# dji_3s_battery.net
KiCad netlist of a schematic drawn in Altium Designer
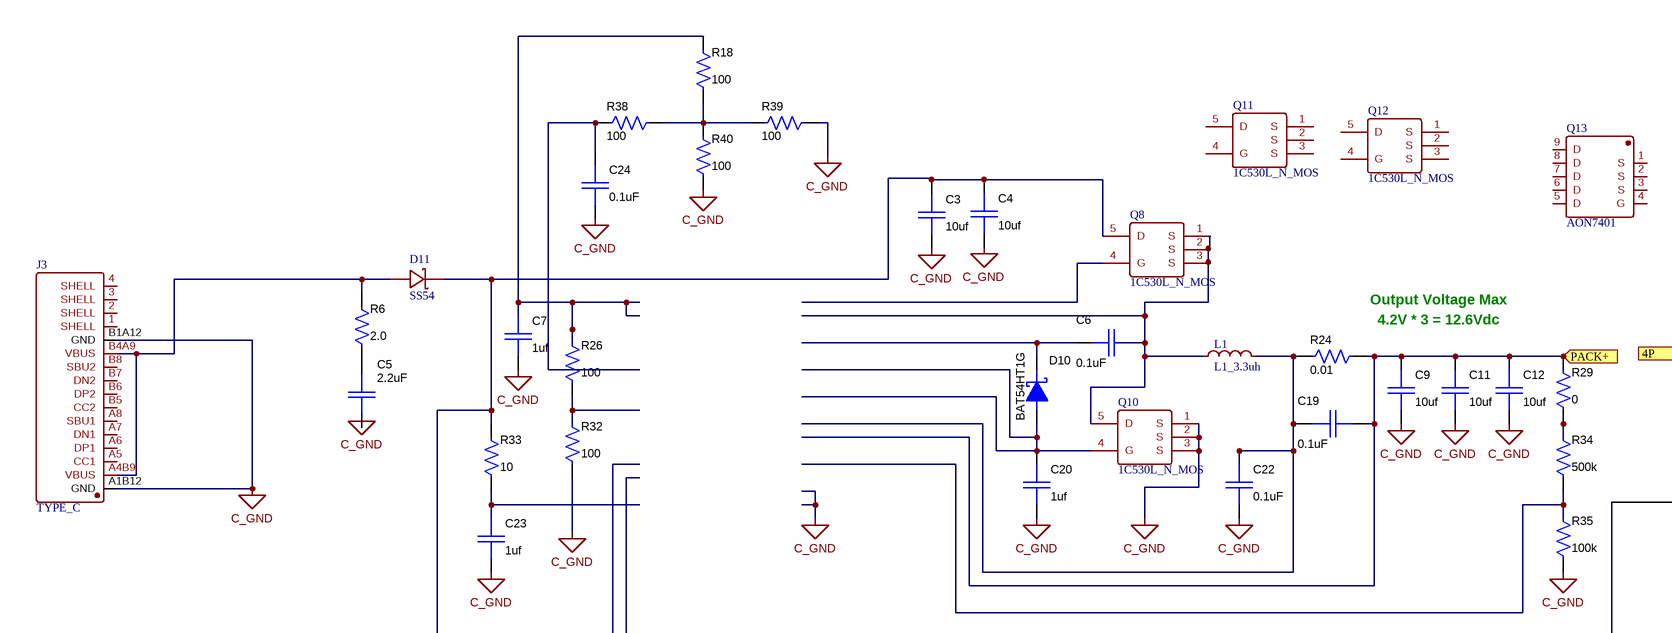
[diagram p0: dji_3s_battery.SchDoc, top left]
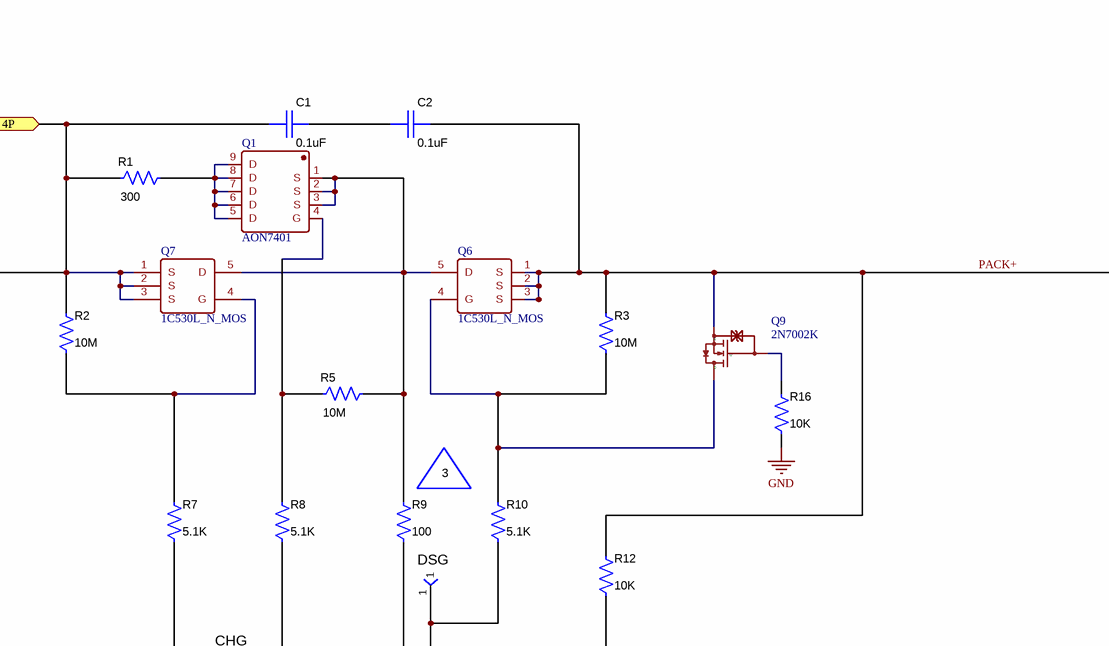
[diagram p1: dji_3s_battery.SchDoc, top right]
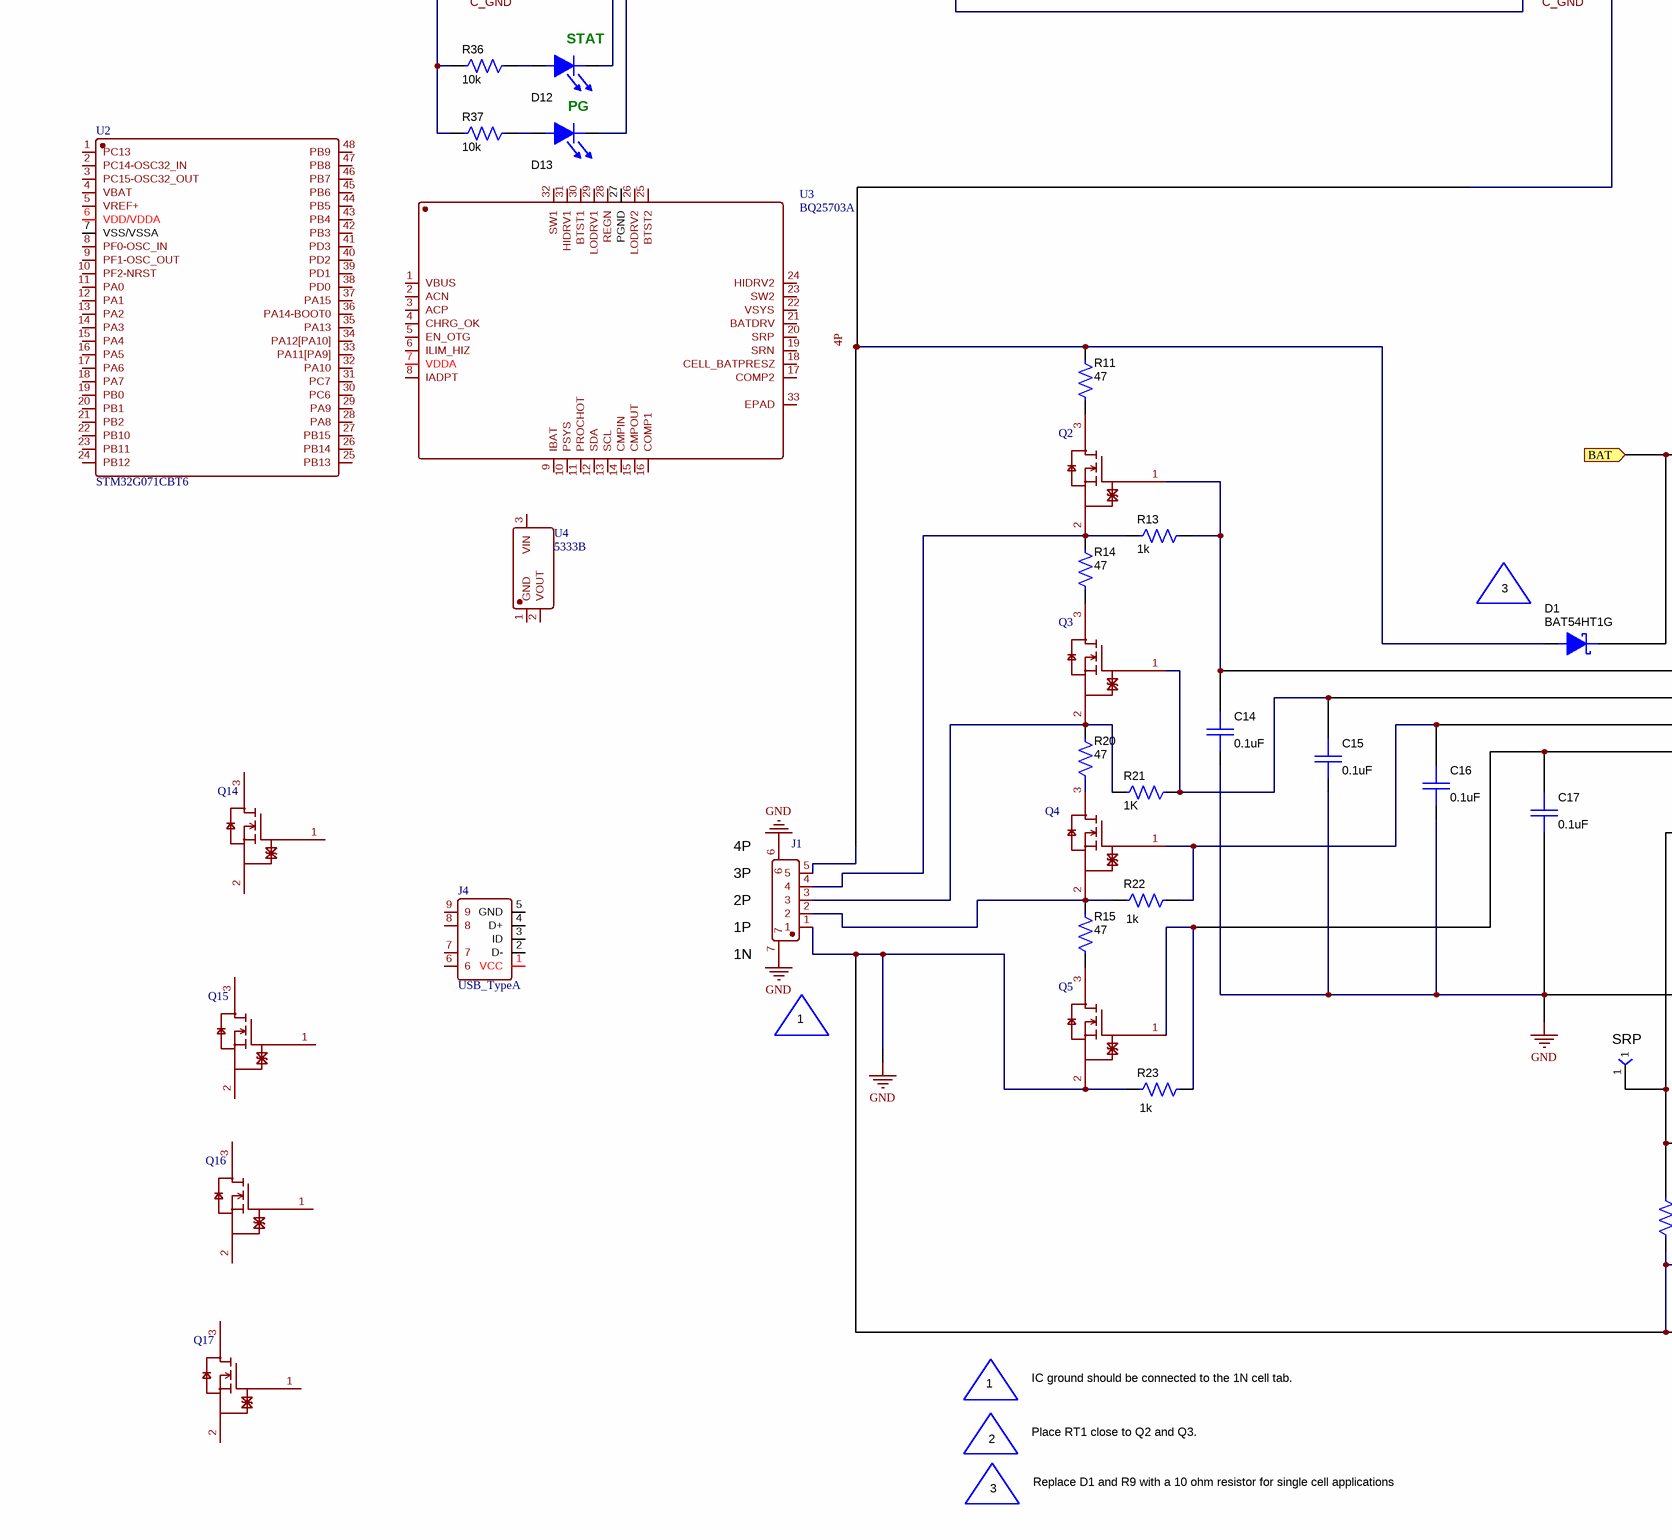
[diagram p2: dji_3s_battery.SchDoc, bottom left]
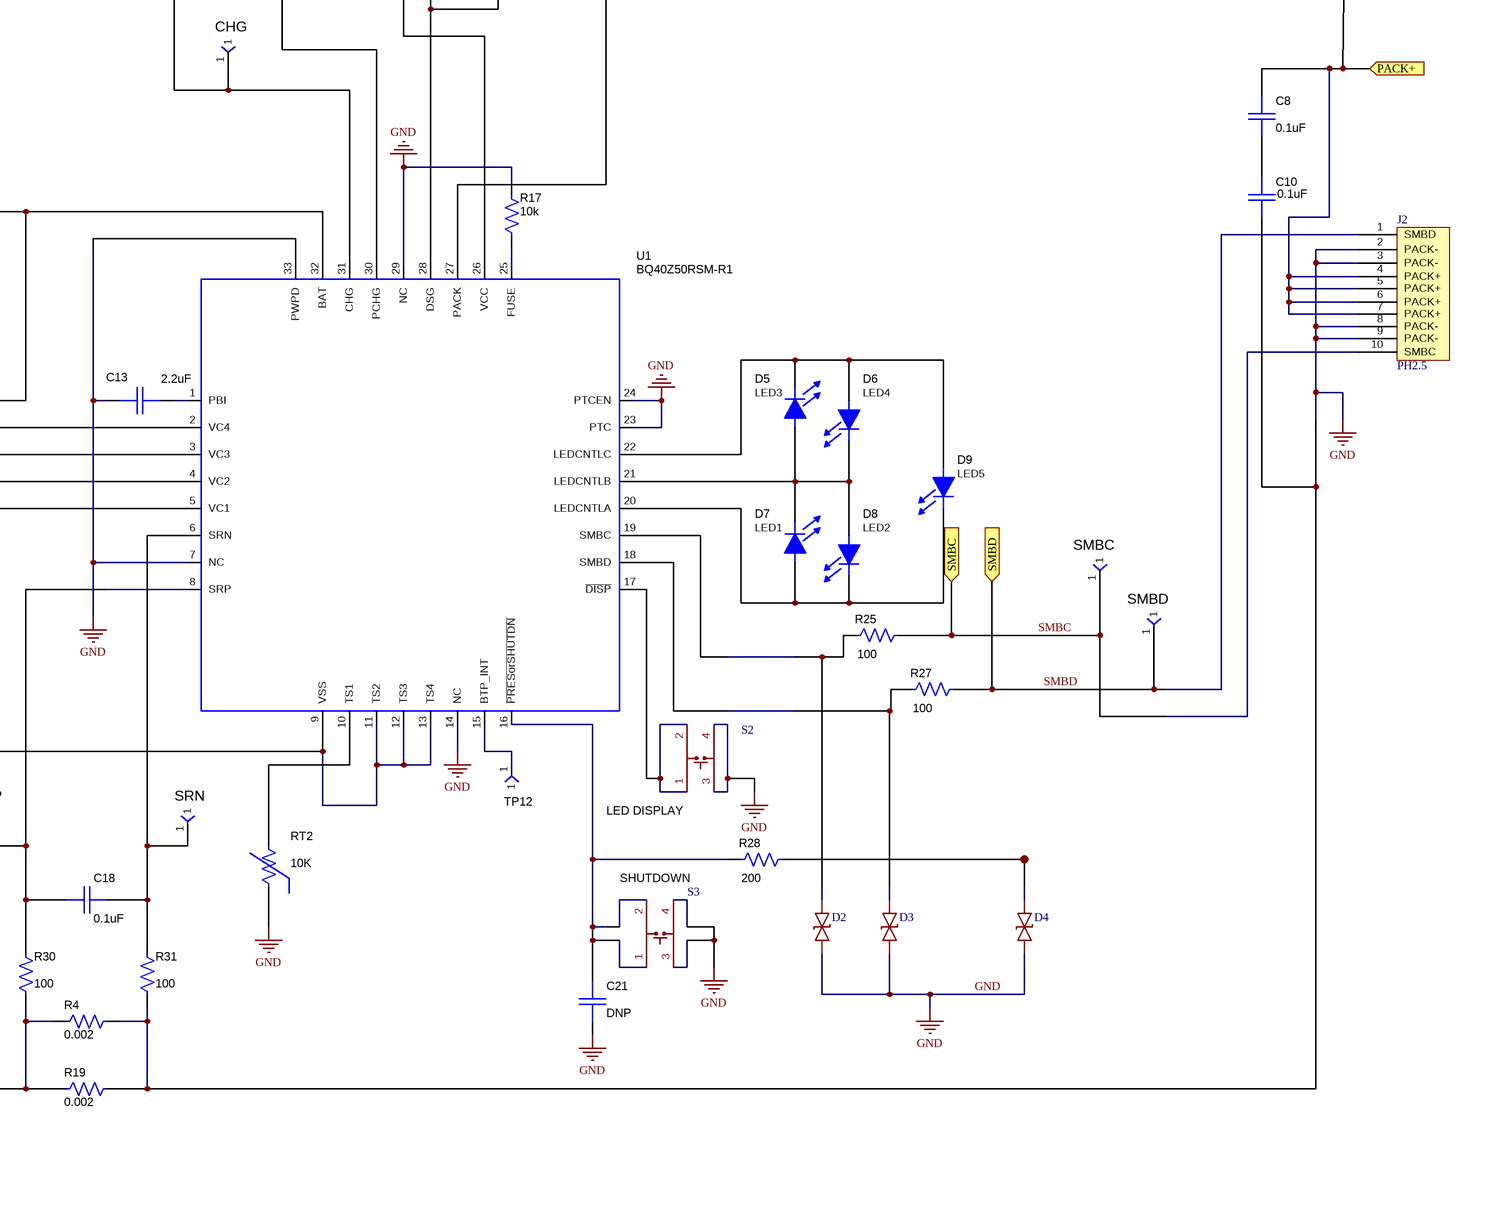
[diagram p3: dji_3s_battery.SchDoc, bottom right]

(export (version "E")
  (design (tool "Eeschema 10.0.6"))
  (components
    (comp (ref "C1")
      (value "0.1uF")
      (footprint "C603")
      (description "Capacitor, Ceramic Chip, 50V, X7R, ±20%")
      (fields (field (name "MANUFACTURER") "Kemet") (field (name "PARTNUMBER") "C0603C104M5RACTU"))
      (libsource (lib "PADSlegacy_Passive") (part "C0603"))
    )
    (comp (ref "C2")
      (value "0.1uF")
      (footprint "C603")
      (description "Capacitor, Ceramic Chip, 50V, X7R, ±20%")
      (fields (field (name "MANUFACTURER") "Kemet") (field (name "PARTNUMBER") "C0603C104M5RACTU"))
      (libsource (lib "PADSlegacy_Passive") (part "C0603"))
    )
    (comp (ref "C3")
      (value "10uf")
      (footprint "C603")
      (description "Capacitor, Ceramic Chip, 50V, X7R, ±20%")
      (fields (field (name "MANUFACTURER") "Kemet") (field (name "PARTNUMBER") "C0603C104M5RACTU"))
      (libsource (lib "PADSlegacy_Passive") (part "C0603"))
    )
    (comp (ref "C4")
      (value "10uf")
      (footprint "C603")
      (description "Capacitor, Ceramic Chip, 50V, X7R, ±20%")
      (fields (field (name "MANUFACTURER") "Kemet") (field (name "PARTNUMBER") "C0603C104M5RACTU"))
      (libsource (lib "PADSlegacy_Passive") (part "C0603"))
    )
    (comp (ref "C5")
      (value "2.2uF")
      (footprint "C0805")
      (description "Capacitor, Ceramic Chip, 25V, X7R ±20%")
      (fields (field (name "MANUFACTURER") "TDK") (field (name "PARTNUMBER") "C2012X7R1E225M085AB"))
      (libsource (lib "PADSlegacy_Passive") (part "C0805"))
    )
    (comp (ref "C6")
      (value "0.1uF")
      (footprint "C603")
      (description "Capacitor, Ceramic Chip, 50V, X7R, ±20%")
      (fields (field (name "MANUFACTURER") "Kemet") (field (name "PARTNUMBER") "C0603C104M5RACTU"))
      (libsource (lib "PADSlegacy_Passive") (part "C0603"))
    )
    (comp (ref "C7")
      (value "1uf")
      (footprint "C603")
      (description "Capacitor, Ceramic Chip, 50V, X7R, ±20%")
      (fields (field (name "MANUFACTURER") "Kemet") (field (name "PARTNUMBER") "C0603C104M5RACTU"))
      (libsource (lib "PADSlegacy_Passive") (part "C0603"))
    )
    (comp (ref "C8")
      (value "0.1uF")
      (footprint "C603")
      (description "Capacitor, Ceramic Chip, 50V, X7R, ±20%")
      (fields (field (name "MANUFACTURER") "Kemet") (field (name "PARTNUMBER") "C0603C104M5RACTU"))
      (libsource (lib "PADSlegacy_Passive") (part "C0603"))
    )
    (comp (ref "C9")
      (value "10uf")
      (footprint "C603")
      (description "Capacitor, Ceramic Chip, 50V, X7R, ±20%")
      (fields (field (name "MANUFACTURER") "Kemet") (field (name "PARTNUMBER") "C0603C104M5RACTU"))
      (libsource (lib "PADSlegacy_Passive") (part "C0603"))
    )
    (comp (ref "C10")
      (value "0.1uF")
      (footprint "C603")
      (description "Capacitor, Ceramic Chip, 50V, X7R, ±20%")
      (fields (field (name "MANUFACTURER") "Kemet") (field (name "PARTNUMBER") "C0603C104M5RACTU"))
      (libsource (lib "PADSlegacy_Passive") (part "C0603"))
    )
    (comp (ref "C11")
      (value "10uf")
      (footprint "C603")
      (description "Capacitor, Ceramic Chip, 50V, X7R, ±20%")
      (fields (field (name "MANUFACTURER") "Kemet") (field (name "PARTNUMBER") "C0603C104M5RACTU"))
      (libsource (lib "PADSlegacy_Passive") (part "C0603"))
    )
    (comp (ref "C12")
      (value "10uf")
      (footprint "C603")
      (description "Capacitor, Ceramic Chip, 50V, X7R, ±20%")
      (fields (field (name "MANUFACTURER") "Kemet") (field (name "PARTNUMBER") "C0603C104M5RACTU"))
      (libsource (lib "PADSlegacy_Passive") (part "C0603"))
    )
    (comp (ref "C13")
      (value "2.2uF")
      (footprint "C0805")
      (description "Capacitor, Ceramic Chip, 25V, X7R ±20%")
      (fields (field (name "MANUFACTURER") "TDK") (field (name "PARTNUMBER") "C2012X7R1E225M085AB"))
      (libsource (lib "PADSlegacy_Passive") (part "C0805"))
    )
    (comp (ref "C14")
      (value "0.1uF")
      (footprint "C603")
      (description "Capacitor, Ceramic Chip, 50V, X7R, ±20%")
      (fields (field (name "MANUFACTURER") "Kemet") (field (name "PARTNUMBER") "C0603C104M5RACTU"))
      (libsource (lib "PADSlegacy_Passive") (part "C0603"))
    )
    (comp (ref "C15")
      (value "0.1uF")
      (footprint "C603")
      (description "Capacitor, Ceramic Chip, 50V, X7R, ±20%")
      (fields (field (name "MANUFACTURER") "Kemet") (field (name "PARTNUMBER") "C0603C104M5RACTU"))
      (libsource (lib "PADSlegacy_Passive") (part "C0603"))
    )
    (comp (ref "C16")
      (value "0.1uF")
      (footprint "C603")
      (description "Capacitor, Ceramic Chip, 50V, X7R, ±20%")
      (fields (field (name "MANUFACTURER") "Kemet") (field (name "PARTNUMBER") "C0603C104M5RACTU"))
      (libsource (lib "PADSlegacy_Passive") (part "C0603"))
    )
    (comp (ref "C17")
      (value "0.1uF")
      (footprint "C603")
      (description "Capacitor, Ceramic Chip, 50V, X7R, ±20%")
      (fields (field (name "MANUFACTURER") "Kemet") (field (name "PARTNUMBER") "C0603C104M5RACTU"))
      (libsource (lib "PADSlegacy_Passive") (part "C0603"))
    )
    (comp (ref "C18")
      (value "0.1uF")
      (footprint "C603")
      (description "Capacitor, Ceramic Chip, 50V, X7R, ±20%")
      (fields (field (name "MANUFACTURER") "Kemet") (field (name "PARTNUMBER") "C0603C104M5RACTU"))
      (libsource (lib "PADSlegacy_Passive") (part "C0603"))
    )
    (comp (ref "C19")
      (value "0.1uF")
      (footprint "C603")
      (description "Capacitor, Ceramic Chip, 50V, X7R, ±20%")
      (fields (field (name "MANUFACTURER") "Kemet") (field (name "PARTNUMBER") "C0603C104M5RACTU"))
      (libsource (lib "PADSlegacy_Passive") (part "C0603"))
    )
    (comp (ref "C20")
      (value "1uf")
      (footprint "C603")
      (description "Capacitor, Ceramic Chip, 50V, X7R, ±20%")
      (fields (field (name "MANUFACTURER") "Kemet") (field (name "PARTNUMBER") "C0603C104M5RACTU"))
      (libsource (lib "PADSlegacy_Passive") (part "C0603"))
    )
    (comp (ref "C21")
      (value "DNP")
      (footprint "C603")
      (description "Capacitor, Ceramic Chip, 50V, X7R, ±20%")
      (fields (field (name "MANUFACTURER") "Kemet") (field (name "PARTNUMBER") "C0603C104M5RACTU"))
      (libsource (lib "PADSlegacy_Passive") (part "C0603"))
    )
    (comp (ref "C22")
      (value "0.1uF")
      (footprint "C603")
      (description "Capacitor, Ceramic Chip, 50V, X7R, ±20%")
      (fields (field (name "MANUFACTURER") "Kemet") (field (name "PARTNUMBER") "C0603C104M5RACTU"))
      (libsource (lib "PADSlegacy_Passive") (part "C0603"))
    )
    (comp (ref "C23")
      (value "1uf")
      (footprint "C603")
      (description "Capacitor, Ceramic Chip, 50V, X7R, ±20%")
      (fields (field (name "MANUFACTURER") "Kemet") (field (name "PARTNUMBER") "C0603C104M5RACTU"))
      (libsource (lib "PADSlegacy_Passive") (part "C0603"))
    )
    (comp (ref "C24")
      (value "0.1uF")
      (footprint "C603")
      (description "Capacitor, Ceramic Chip, 50V, X7R, ±20%")
      (fields (field (name "MANUFACTURER") "Kemet") (field (name "PARTNUMBER") "C0603C104M5RACTU"))
      (libsource (lib "PADSlegacy_Passive") (part "C0603"))
    )
    (comp (ref "D1")
      (value "BAT54HT1G")
      (footprint "SOD-323")
      (description "Diode, Schottky, 200-mA, 30-V")
      (fields (field (name "MANUFACTURER") "On Semi") (field (name "Comment") "D-BAT54HT1"))
      (libsource (lib "PADSlegacy_Active") (part "D-BAT54HT1"))
    )
    (comp (ref "D2")
      (value "ESD_Diode")
      (footprint "ESD_Diode")
      (libsource (lib "BQ4050") (part "ESD_Diode"))
    )
    (comp (ref "D3")
      (value "ESD_Diode")
      (footprint "ESD_Diode")
      (libsource (lib "BQ4050") (part "ESD_Diode"))
    )
    (comp (ref "D4")
      (value "ESD_Diode")
      (footprint "ESD_Diode")
      (libsource (lib "BQ4050") (part "ESD_Diode"))
    )
    (comp (ref "D5")
      (value "D_LED_SML-LXR1206USBC-TR")
      (footprint "LED0805")
      (description "Diode, LED, 2X3mm 565nm GRN WTR CLR SMD")
      (fields (field (name "PARTNUMBER") "SML-LX23GC") (field (name "MANUFACTURER") "Lumex"))
      (libsource (lib "PADSlegacy_Active") (part "D_LED_SML-LXR1206USBC-TR"))
    )
    (comp (ref "D6")
      (value "D_LED_SML-LXR1206USBC-TR")
      (footprint "LED0805")
      (description "Diode, LED, 2X3mm 565nm GRN WTR CLR SMD")
      (fields (field (name "PARTNUMBER") "SML-LX23GC") (field (name "MANUFACTURER") "Lumex"))
      (libsource (lib "PADSlegacy_Active") (part "D_LED_SML-LXR1206USBC-TR"))
    )
    (comp (ref "D7")
      (value "D_LED_SML-LXR1206USBC-TR")
      (footprint "LED0805")
      (description "Diode, LED, 2X3mm 565nm GRN WTR CLR SMD")
      (fields (field (name "PARTNUMBER") "SML-LX23GC") (field (name "MANUFACTURER") "Lumex"))
      (libsource (lib "PADSlegacy_Active") (part "D_LED_SML-LXR1206USBC-TR"))
    )
    (comp (ref "D8")
      (value "D_LED_SML-LXR1206USBC-TR")
      (footprint "LED0805")
      (description "Diode, LED, 2X3mm 565nm GRN WTR CLR SMD")
      (fields (field (name "PARTNUMBER") "SML-LX23GC") (field (name "MANUFACTURER") "Lumex"))
      (libsource (lib "PADSlegacy_Active") (part "D_LED_SML-LXR1206USBC-TR"))
    )
    (comp (ref "D9")
      (value "D_LED_SML-LXR1206USBC-TR")
      (footprint "LED0805")
      (description "Diode, LED, 2X3mm 565nm GRN WTR CLR SMD")
      (fields (field (name "PARTNUMBER") "SML-LX23GC") (field (name "MANUFACTURER") "Lumex"))
      (libsource (lib "PADSlegacy_Active") (part "D_LED_SML-LXR1206USBC-TR"))
    )
    (comp (ref "D10")
      (value "BAT54HT1G")
      (footprint "SOD-323")
      (description "Diode, Schottky, 200-mA, 30-V")
      (fields (field (name "MANUFACTURER") "On Semi") (field (name "Comment") "D-BAT54HT1"))
      (libsource (lib "PADSlegacy_Active") (part "D-BAT54HT1"))
    )
    (comp (ref "D11") (value "SS54") (footprint "SMA(DO-214AC)") (libsource (lib "BQ4050") (part "SS54")))
    (comp (ref "D12")
      (value "D_LED_SML-LXR1206USBC-TR")
      (footprint "LED0805")
      (description "Diode, LED, 2X3mm 565nm GRN WTR CLR SMD")
      (fields (field (name "PARTNUMBER") "SML-LX23GC") (field (name "MANUFACTURER") "Lumex"))
      (libsource (lib "PADSlegacy_Active") (part "D_LED_SML-LXR1206USBC-TR"))
    )
    (comp (ref "D13")
      (value "D_LED_SML-LXR1206USBC-TR")
      (footprint "LED0805")
      (description "Diode, LED, 2X3mm 565nm GRN WTR CLR SMD")
      (fields (field (name "PARTNUMBER") "SML-LX23GC") (field (name "MANUFACTURER") "Lumex"))
      (libsource (lib "PADSlegacy_Active") (part "D_LED_SML-LXR1206USBC-TR"))
    )
    (comp (ref "J1") (value "SMD_1.25") (footprint "SMD_1.25") (libsource (lib "BQ4050") (part "SMD_1.25")))
    (comp (ref "J2") (value "PH2.5") (footprint "PH2.5") (libsource (lib "BQ4050") (part "PH2.5")))
    (comp (ref "J3") (value "TYPE_C") (footprint "TYPE_C") (libsource (lib "BQ4050") (part "TYPE_C")))
    (comp (ref "J4")
      (value "USB_TypeA")
      (footprint "USB_TypeA")
      (libsource (lib "BQ4050") (part "USB_TypeA"))
    )
    (comp (ref "L1") (value "L1_3.3uh") (footprint "3.3uh") (libsource (lib "BQ4050") (part "L1_3.3uh")))
    (comp (ref "Q1") (value "AON7401") (footprint "DFN-8") (libsource (lib "BQ4050") (part "AON7401")))
    (comp (ref "Q2")
      (value "DMN601K")
      (footprint "SOT-23 - duplicate")
      (libsource (lib "BQ4050") (part "DMN601K"))
    )
    (comp (ref "Q3")
      (value "DMN601K")
      (footprint "SOT-23 - duplicate")
      (libsource (lib "BQ4050") (part "DMN601K"))
    )
    (comp (ref "Q4")
      (value "DMN601K")
      (footprint "SOT-23 - duplicate")
      (libsource (lib "BQ4050") (part "DMN601K"))
    )
    (comp (ref "Q5")
      (value "DMN601K")
      (footprint "SOT-23 - duplicate")
      (libsource (lib "BQ4050") (part "DMN601K"))
    )
    (comp (ref "Q6")
      (value "1C530L_N_MOS")
      (footprint "LFPAK")
      (libsource (lib "BQ4050") (part "1C530L_N_MOS"))
    )
    (comp (ref "Q7")
      (value "1C530L_N_MOS")
      (footprint "LFPAK")
      (libsource (lib "BQ4050") (part "1C530L_N_MOS"))
    )
    (comp (ref "Q8")
      (value "1C530L_N_MOS")
      (footprint "LFPAK")
      (libsource (lib "BQ4050") (part "1C530L_N_MOS"))
    )
    (comp (ref "Q9") (value "2N7002K") (footprint "2N7002K") (libsource (lib "BQ4050") (part "2N7002K")))
    (comp (ref "Q10")
      (value "1C530L_N_MOS")
      (footprint "LFPAK")
      (libsource (lib "BQ4050") (part "1C530L_N_MOS"))
    )
    (comp (ref "Q11")
      (value "1C530L_N_MOS")
      (footprint "LFPAK")
      (libsource (lib "BQ4050") (part "1C530L_N_MOS"))
    )
    (comp (ref "Q12")
      (value "1C530L_N_MOS")
      (footprint "LFPAK")
      (libsource (lib "BQ4050") (part "1C530L_N_MOS"))
    )
    (comp (ref "Q13") (value "AON7401") (footprint "DFN-8") (libsource (lib "BQ4050") (part "AON7401")))
    (comp (ref "Q14")
      (value "DMN601K")
      (footprint "SOT-23 - duplicate")
      (libsource (lib "BQ4050") (part "DMN601K"))
    )
    (comp (ref "Q15")
      (value "DMN601K")
      (footprint "SOT-23 - duplicate")
      (libsource (lib "BQ4050") (part "DMN601K"))
    )
    (comp (ref "Q16")
      (value "DMN601K")
      (footprint "SOT-23 - duplicate")
      (libsource (lib "BQ4050") (part "DMN601K"))
    )
    (comp (ref "Q17")
      (value "DMN601K")
      (footprint "SOT-23 - duplicate")
      (libsource (lib "BQ4050") (part "DMN601K"))
    )
    (comp (ref "R1")
      (value "300")
      (footprint "R2512")
      (description "Resistor, Chip 1W, 5%")
      (fields (field (name "PARTNUMBER") "CRCW2512300RJNEG") (field (name "MANUFACTURER") "Vishay-Dale"))
      (libsource (lib "PADSlegacy_Passive") (part "R2512_5%"))
    )
    (comp (ref "R2")
      (value "10M")
      (footprint "0603")
      (description "Resistor, Chip, 1/10W, 5%")
      (fields (field (name "PARTNUMBER") "CRCW060310M0JNEA") (field (name "MANUFACTURER") "Vishay-Dale"))
      (libsource (lib "PADSlegacy_Passive") (part "R0603_1%"))
    )
    (comp (ref "R3")
      (value "10M")
      (footprint "0603")
      (description "Resistor, Chip, 1/10W, 5%")
      (fields (field (name "PARTNUMBER") "CRCW060310M0JNEA") (field (name "MANUFACTURER") "Vishay-Dale"))
      (libsource (lib "PADSlegacy_Passive") (part "R0603_1%"))
    )
    (comp (ref "R4")
      (value "0.002")
      (footprint "R2512")
      (description "Resistor, Chip 1W, 5%")
      (fields (field (name "PARTNUMBER") "CRCW2512300RJNEG") (field (name "MANUFACTURER") "Vishay-Dale"))
      (libsource (lib "BQ4050") (part "R2512_5%"))
    )
    (comp (ref "R5")
      (value "10M")
      (footprint "0603")
      (description "Resistor, Chip, 1/10W, 5%")
      (fields (field (name "PARTNUMBER") "CRCW060310M0JNEA") (field (name "MANUFACTURER") "Vishay-Dale"))
      (libsource (lib "PADSlegacy_Passive") (part "R0603_1%"))
    )
    (comp (ref "R6")
      (value "2.0")
      (footprint "0603")
      (description "Resistor, Chip, 1/10W, 5%")
      (fields (field (name "PARTNUMBER") "CRCW0603100RJNEAHP") (field (name "MANUFACTURER") "Vishay-Dale"))
      (libsource (lib "PADSlegacy_Passive") (part "R0603_1%"))
    )
    (comp (ref "R7")
      (value "5.1K")
      (footprint "0603")
      (description "Resistor, Chip, 1/10W, 5%")
      (fields (field (name "PARTNUMBER") "CRCW06035K10JNEA") (field (name "MANUFACTURER") "Vishay-Dale"))
      (libsource (lib "PADSlegacy_Passive") (part "R0603_1%"))
    )
    (comp (ref "R8")
      (value "5.1K")
      (footprint "0603")
      (description "Resistor, Chip, 1/10W, 5%")
      (fields (field (name "PARTNUMBER") "CRCW06035K10JNEA") (field (name "MANUFACTURER") "Vishay-Dale"))
      (libsource (lib "PADSlegacy_Passive") (part "R0603_1%"))
    )
    (comp (ref "R9")
      (value "100")
      (footprint "0603")
      (description "Resistor, Chip, 1/10W, 5%")
      (fields (field (name "PARTNUMBER") "CRCW0603100RJNEAHP") (field (name "MANUFACTURER") "Vishay-Dale"))
      (libsource (lib "PADSlegacy_Passive") (part "R0603_1%"))
    )
    (comp (ref "R10")
      (value "5.1K")
      (footprint "0603")
      (description "Resistor, Chip, 1/10W, 5%")
      (fields (field (name "PARTNUMBER") "CRCW06035K10JNEA") (field (name "MANUFACTURER") "Vishay-Dale"))
      (libsource (lib "PADSlegacy_Passive") (part "R0603_1%"))
    )
    (comp (ref "R11")
      (value "47")
      (footprint "R1206")
      (description "Resistor, Chip 1 watt, ±1%, 50 ppm")
      (fields (field (name "PARTNUMBER") "CSR1206-0R001F1") (field (name "MANUFACTURER") "Reidon"))
      (libsource (lib "BQ4050") (part "R1206_1%"))
    )
    (comp (ref "R12")
      (value "10K")
      (footprint "0603")
      (description "Resistor, Chip, 1/10W, 5%")
      (fields (field (name "PARTNUMBER") "CRCW060310K0JNEA") (field (name "MANUFACTURER") "Vishay-Dale"))
      (libsource (lib "PADSlegacy_Passive") (part "R0603_1%"))
    )
    (comp (ref "R13")
      (value "1k")
      (footprint "0603")
      (description "Resistor, Chip, 1/10W, 5%")
      (fields (field (name "PARTNUMBER") "CRCW0603100RJNEAHP") (field (name "MANUFACTURER") "Vishay-Dale"))
      (libsource (lib "PADSlegacy_Passive") (part "R0603_1%"))
    )
    (comp (ref "R14")
      (value "47")
      (footprint "R1206")
      (description "Resistor, Chip 1 watt, ±1%, 50 ppm")
      (fields (field (name "PARTNUMBER") "CSR1206-0R001F1") (field (name "MANUFACTURER") "Reidon"))
      (libsource (lib "BQ4050") (part "R1206_1%"))
    )
    (comp (ref "R15")
      (value "47")
      (footprint "R1206")
      (description "Resistor, Chip 1 watt, ±1%, 50 ppm")
      (fields (field (name "PARTNUMBER") "CSR1206-0R001F1") (field (name "MANUFACTURER") "Reidon"))
      (libsource (lib "BQ4050") (part "R1206_1%"))
    )
    (comp (ref "R16")
      (value "10K")
      (footprint "0603")
      (description "Resistor, Chip, 1/10W, 5%")
      (fields (field (name "PARTNUMBER") "CRCW060310M0JNEA") (field (name "MANUFACTURER") "Vishay-Dale"))
      (libsource (lib "PADSlegacy_Passive") (part "R0603_1%"))
    )
    (comp (ref "R17")
      (value "10k")
      (footprint "0603")
      (description "Resistor, Chip, 1/10W, 5%")
      (fields (field (name "PARTNUMBER") "CRCW06035K10JNEA") (field (name "MANUFACTURER") "Vishay-Dale"))
      (libsource (lib "PADSlegacy_Passive") (part "R0603_1%"))
    )
    (comp (ref "R18")
      (value "100")
      (footprint "0603")
      (description "Resistor, Chip, 1/10W, 5%")
      (fields (field (name "PARTNUMBER") "CRCW0603100RJNEAHP") (field (name "MANUFACTURER") "Vishay-Dale"))
      (libsource (lib "PADSlegacy_Passive") (part "R0603_1%"))
    )
    (comp (ref "R19")
      (value "0.002")
      (footprint "R2512")
      (description "Resistor, Chip 1W, 5%")
      (fields (field (name "PARTNUMBER") "CRCW2512300RJNEG") (field (name "MANUFACTURER") "Vishay-Dale"))
      (libsource (lib "BQ4050") (part "R2512_5%"))
    )
    (comp (ref "R20")
      (value "47")
      (footprint "R1206")
      (description "Resistor, Chip 1 watt, ±1%, 50 ppm")
      (fields (field (name "PARTNUMBER") "CSR1206-0R001F1") (field (name "MANUFACTURER") "Reidon"))
      (libsource (lib "BQ4050") (part "R1206_1%"))
    )
    (comp (ref "R21")
      (value "1K")
      (footprint "0603")
      (description "Resistor, Chip, 1/10W, 5%")
      (fields (field (name "PARTNUMBER") "CRCW0603100RJNEAHP") (field (name "MANUFACTURER") "Vishay-Dale"))
      (libsource (lib "PADSlegacy_Passive") (part "R0603_1%"))
    )
    (comp (ref "R22")
      (value "1k")
      (footprint "0603")
      (description "Resistor, Chip, 1/10W, 5%")
      (fields (field (name "PARTNUMBER") "CRCW0603100RJNEAHP") (field (name "MANUFACTURER") "Vishay-Dale"))
      (libsource (lib "PADSlegacy_Passive") (part "R0603_1%"))
    )
    (comp (ref "R23")
      (value "1k")
      (footprint "0603")
      (description "Resistor, Chip, 1/10W, 5%")
      (fields (field (name "PARTNUMBER") "CRCW0603100RJNEAHP") (field (name "MANUFACTURER") "Vishay-Dale"))
      (libsource (lib "PADSlegacy_Passive") (part "R0603_1%"))
    )
    (comp (ref "R24")
      (value "0.01")
      (footprint "R2512")
      (description "Resistor, Chip 1W, 5%")
      (fields (field (name "PARTNUMBER") "CRCW2512300RJNEG") (field (name "MANUFACTURER") "Vishay-Dale"))
      (libsource (lib "BQ4050") (part "R2512_5%"))
    )
    (comp (ref "R25")
      (value "100")
      (footprint "0603")
      (description "Resistor, Chip, 1/10W, 5%")
      (fields (field (name "PARTNUMBER") "CRCW0603100RJNEAHP") (field (name "MANUFACTURER") "Vishay-Dale"))
      (libsource (lib "PADSlegacy_Passive") (part "R0603_1%"))
    )
    (comp (ref "R26")
      (value "100")
      (footprint "0603")
      (description "Resistor, Chip, 1/10W, 5%")
      (fields (field (name "PARTNUMBER") "CRCW0603100RJNEAHP") (field (name "MANUFACTURER") "Vishay-Dale"))
      (libsource (lib "PADSlegacy_Passive") (part "R0603_1%"))
    )
    (comp (ref "R27")
      (value "100")
      (footprint "0603")
      (description "Resistor, Chip, 1/10W, 5%")
      (fields (field (name "PARTNUMBER") "CRCW0603100RJNEAHP") (field (name "MANUFACTURER") "Vishay-Dale"))
      (libsource (lib "PADSlegacy_Passive") (part "R0603_1%"))
    )
    (comp (ref "R28")
      (value "200")
      (footprint "0603")
      (description "Resistor, Chip, 1/16W, 5%")
      (fields (field (name "PARTNUMBER") "CRCW0603200RJNEA") (field (name "MANUFACTURER") "Vishay-Dale"))
      (libsource (lib "PADSlegacy_Passive") (part "R0603_1%"))
    )
    (comp (ref "R29")
      (value "0")
      (footprint "0603")
      (description "Resistor, Chip, 1/10W, 5%")
      (fields (field (name "PARTNUMBER") "CRCW0603100RJNEAHP") (field (name "MANUFACTURER") "Vishay-Dale"))
      (libsource (lib "PADSlegacy_Passive") (part "R0603_1%"))
    )
    (comp (ref "R30")
      (value "100")
      (footprint "0603")
      (description "Resistor, Chip, 1/10W, 5%")
      (fields (field (name "PARTNUMBER") "CRCW0603100RJNEAHP") (field (name "MANUFACTURER") "Vishay-Dale"))
      (libsource (lib "PADSlegacy_Passive") (part "R0603_1%"))
    )
    (comp (ref "R31")
      (value "100")
      (footprint "0603")
      (description "Resistor, Chip, 1/10W, 5%")
      (fields (field (name "PARTNUMBER") "CRCW0603100RJNEAHP") (field (name "MANUFACTURER") "Vishay-Dale"))
      (libsource (lib "PADSlegacy_Passive") (part "R0603_1%"))
    )
    (comp (ref "R32")
      (value "100")
      (footprint "0603")
      (description "Resistor, Chip, 1/10W, 5%")
      (fields (field (name "PARTNUMBER") "CRCW0603100RJNEAHP") (field (name "MANUFACTURER") "Vishay-Dale"))
      (libsource (lib "PADSlegacy_Passive") (part "R0603_1%"))
    )
    (comp (ref "R33")
      (value "10")
      (footprint "0603")
      (description "Resistor, Chip, 1/10W, 5%")
      (fields (field (name "PARTNUMBER") "CRCW0603100RJNEAHP") (field (name "MANUFACTURER") "Vishay-Dale"))
      (libsource (lib "PADSlegacy_Passive") (part "R0603_1%"))
    )
    (comp (ref "R34")
      (value "500k")
      (footprint "0603")
      (description "Resistor, Chip, 1/10W, 5%")
      (fields (field (name "PARTNUMBER") "CRCW0603100RJNEAHP") (field (name "MANUFACTURER") "Vishay-Dale"))
      (libsource (lib "PADSlegacy_Passive") (part "R0603_1%"))
    )
    (comp (ref "R35")
      (value "100k")
      (footprint "0603")
      (description "Resistor, Chip, 1/10W, 5%")
      (fields (field (name "PARTNUMBER") "CRCW0603100RJNEAHP") (field (name "MANUFACTURER") "Vishay-Dale"))
      (libsource (lib "PADSlegacy_Passive") (part "R0603_1%"))
    )
    (comp (ref "R36")
      (value "10k")
      (footprint "0603")
      (description "Resistor, Chip, 1/10W, 5%")
      (fields (field (name "PARTNUMBER") "CRCW0603100RJNEAHP") (field (name "MANUFACTURER") "Vishay-Dale"))
      (libsource (lib "PADSlegacy_Passive") (part "R0603_1%"))
    )
    (comp (ref "R37")
      (value "10k")
      (footprint "0603")
      (description "Resistor, Chip, 1/10W, 5%")
      (fields (field (name "PARTNUMBER") "CRCW0603100RJNEAHP") (field (name "MANUFACTURER") "Vishay-Dale"))
      (libsource (lib "PADSlegacy_Passive") (part "R0603_1%"))
    )
    (comp (ref "R38")
      (value "100")
      (footprint "0603")
      (description "Resistor, Chip, 1/10W, 5%")
      (fields (field (name "PARTNUMBER") "CRCW0603100RJNEAHP") (field (name "MANUFACTURER") "Vishay-Dale"))
      (libsource (lib "PADSlegacy_Passive") (part "R0603_1%"))
    )
    (comp (ref "R39")
      (value "100")
      (footprint "0603")
      (description "Resistor, Chip, 1/10W, 5%")
      (fields (field (name "PARTNUMBER") "CRCW0603100RJNEAHP") (field (name "MANUFACTURER") "Vishay-Dale"))
      (libsource (lib "PADSlegacy_Passive") (part "R0603_1%"))
    )
    (comp (ref "R40")
      (value "100")
      (footprint "0603")
      (description "Resistor, Chip, 1/10W, 5%")
      (fields (field (name "PARTNUMBER") "CRCW0603100RJNEAHP") (field (name "MANUFACTURER") "Vishay-Dale"))
      (libsource (lib "PADSlegacy_Passive") (part "R0603_1%"))
    )
    (comp (ref "RT2")
      (value "10K")
      (footprint "C0805")
      (description "Thermistor, NTC, 3-A")
      (fields (field (name "MANUFACTURER") "Semitec") (field (name "PARTNUMBER") "103AT-2"))
      (libsource (lib "PADSlegacy_Passive") (part "THERMISTOR-103AT"))
    )
    (comp (ref "S2") (value "SW_SMD") (footprint "SW_SMD") (libsource (lib "BQ4050") (part "SW_SMD")))
    (comp (ref "S3") (value "SW_SMD") (footprint "SW_SMD") (libsource (lib "BQ4050") (part "SW_SMD")))
    (comp (ref "TP1")
      (value "TP_40_SMT")
      (footprint "TP_40_SMT")
      (description "Test point, 40 mil SMT")
      (fields (field (name "MANUFACTURER") "None"))
      (libsource (lib "PADSlegacy_Hardware") (part "TP_40_SMT"))
    )
    (comp (ref "TP2")
      (value "TP_.040_SMT")
      (footprint "TP_.040_SMT")
      (description "Test point, 40 mil SMT")
      (fields (field (name "MANUFACTURER") "None"))
      (libsource (lib "PADSlegacy_Hardware") (part "TP_.040_SMT"))
    )
    (comp (ref "TP5")
      (value "TP_.040_SMT")
      (footprint "TP_.040_SMT")
      (description "Test point, 40 mil SMT")
      (fields (field (name "MANUFACTURER") "None"))
      (libsource (lib "PADSlegacy_Hardware") (part "TP_.040_SMT"))
    )
    (comp (ref "TP6")
      (value "TP_.040_SMT")
      (footprint "TP_.040_SMT")
      (description "Test point, 40 mil SMT")
      (fields (field (name "MANUFACTURER") "None"))
      (libsource (lib "PADSlegacy_Hardware") (part "TP_.040_SMT"))
    )
    (comp (ref "TP9")
      (value "TP_.040_SMT")
      (footprint "TP_.040_SMT")
      (description "Test point, 40 mil SMT")
      (fields (field (name "MANUFACTURER") "None"))
      (libsource (lib "PADSlegacy_Hardware") (part "TP_.040_SMT"))
    )
    (comp (ref "TP10")
      (value "TP_.040_SMT")
      (footprint "TP_.040_SMT")
      (description "Test point, 40 mil SMT")
      (fields (field (name "MANUFACTURER") "None"))
      (libsource (lib "PADSlegacy_Hardware") (part "TP_.040_SMT"))
    )
    (comp (ref "TP12")
      (value "TP_40_SMT")
      (footprint "TP_40_SMT")
      (description "Test point, 40 mil SMT")
      (fields (field (name "MANUFACTURER") "None"))
      (libsource (lib "PADSlegacy_Hardware") (part "TP_40_SMT"))
    )
    (comp (ref "U1")
      (value "BQ40Z50RSM-R1")
      (footprint "QFP-32P_(RSM)")
      (description "IC, 2 to 4-Series Li-Ion Battery Pack Manager")
      (fields (field (name "MANUFACTURER") "TI") (field (name "Comment") "BQ40Z55RSM"))
      (libsource (lib "BQ4050") (part "BQ40Z55RSM"))
    )
    (comp (ref "U2")
      (value "STM32G071CBT6")
      (footprint "STM32G071CBT6")
      (libsource (lib "BQ4050") (part "STM32G071CBT6"))
    )
    (comp (ref "U3") (value "BQ25703A") (footprint "BQ25703A") (libsource (lib "BQ4050") (part "BQ25703A")))
    (comp (ref "U4")
      (value "5333B")
      (footprint "SOT-23 - duplicate")
      (libsource (lib "BQ4050") (part "5333B"))
    )
  )
  (nets
    (net (code "1") (name "/4P") (class "Default")
      (node (ref "C1") (pin "2") (pinfunction "2_2") (pintype "passive"))
      (node (ref "D1") (pin "2") (pinfunction "A_2") (pintype "passive"))
      (node (ref "J1") (pin "5") (pinfunction "5_5") (pintype "passive"))
      (node (ref "Q7") (pin "1") (pinfunction "S_1") (pintype "passive"))
      (node (ref "Q7") (pin "2") (pinfunction "S_2") (pintype "passive"))
      (node (ref "Q7") (pin "3") (pinfunction "S_3") (pintype "passive"))
      (node (ref "R1") (pin "1") (pinfunction "1_1") (pintype "passive"))
      (node (ref "R11") (pin "1") (pinfunction "1_1") (pintype "passive"))
      (node (ref "R2") (pin "2") (pinfunction "2_2") (pintype "passive"))
    )
    (net (code "2") (name "/BAT") (class "Default")
      (node (ref "D1") (pin "1") (pinfunction "C_1") (pintype "passive"))
      (node (ref "U1") (pin "32") (pinfunction "BAT_32") (pintype "passive"))
    )
    (net (code "3") (name "/PACK+") (class "Default")
      (node (ref "C11") (pin "2") (pinfunction "2_2") (pintype "passive"))
      (node (ref "C12") (pin "2") (pinfunction "2_2") (pintype "passive"))
      (node (ref "C19") (pin "1") (pinfunction "1_1") (pintype "passive"))
      (node (ref "C2") (pin "1") (pinfunction "1_1") (pintype "passive"))
      (node (ref "C8") (pin "2") (pinfunction "2_2") (pintype "passive"))
      (node (ref "C9") (pin "2") (pinfunction "2_2") (pintype "passive"))
      (node (ref "J2") (pin "4") (pinfunction "PACK+_4") (pintype "passive"))
      (node (ref "J2") (pin "5") (pinfunction "PACK+_5") (pintype "passive"))
      (node (ref "J2") (pin "6") (pinfunction "PACK+_6") (pintype "passive"))
      (node (ref "J2") (pin "7") (pinfunction "PACK+_7") (pintype "passive"))
      (node (ref "Q6") (pin "1") (pinfunction "S_1") (pintype "passive"))
      (node (ref "Q6") (pin "2") (pinfunction "S_2") (pintype "passive"))
      (node (ref "Q6") (pin "3") (pinfunction "S_3") (pintype "passive"))
      (node (ref "Q9") (pin "2") (pinfunction "S_2") (pintype "passive"))
      (node (ref "R12") (pin "2") (pinfunction "2_2") (pintype "passive"))
      (node (ref "R24") (pin "2") (pinfunction "2_2") (pintype "passive"))
      (node (ref "R29") (pin "2") (pinfunction "2_2") (pintype "passive"))
      (node (ref "R3") (pin "2") (pinfunction "2_2") (pintype "passive"))
    )
    (net (code "4") (name "/SMBC") (class "Default")
      (node (ref "J2") (pin "10") (pinfunction "SMBC_10") (pintype "passive"))
      (node (ref "R25") (pin "2") (pinfunction "2_2") (pintype "passive"))
      (node (ref "TP9") (pin "1") (pinfunction "1_1") (pintype "passive"))
    )
    (net (code "5") (name "/SMBD") (class "Default")
      (node (ref "J2") (pin "1") (pinfunction "SMBD_1") (pintype "passive"))
      (node (ref "R27") (pin "2") (pinfunction "2_2") (pintype "passive"))
      (node (ref "TP10") (pin "1") (pinfunction "1_1") (pintype "passive"))
    )
    (net (code "6") (name "C_GND") (class "Default")
      (node (ref "C11") (pin "1") (pinfunction "1_1") (pintype "passive"))
      (node (ref "C12") (pin "1") (pinfunction "1_1") (pintype "passive"))
      (node (ref "C20") (pin "1") (pinfunction "1_1") (pintype "passive"))
      (node (ref "C22") (pin "1") (pinfunction "1_1") (pintype "passive"))
      (node (ref "C23") (pin "1") (pinfunction "1_1") (pintype "passive"))
      (node (ref "C24") (pin "1") (pinfunction "1_1") (pintype "passive"))
      (node (ref "C3") (pin "1") (pinfunction "1_1") (pintype "passive"))
      (node (ref "C4") (pin "1") (pinfunction "1_1") (pintype "passive"))
      (node (ref "C7") (pin "1") (pinfunction "1_1") (pintype "passive"))
      (node (ref "C9") (pin "1") (pinfunction "1_1") (pintype "passive"))
      (node (ref "J3") (pin "A1B12") (pinfunction "GND_A1B12") (pintype "passive"))
      (node (ref "J3") (pin "B1A12") (pinfunction "GND_B1A12") (pintype "passive"))
      (node (ref "Q10") (pin "1") (pinfunction "S_1") (pintype "passive"))
      (node (ref "Q10") (pin "2") (pinfunction "S_2") (pintype "passive"))
      (node (ref "Q10") (pin "3") (pinfunction "S_3") (pintype "passive"))
      (node (ref "R32") (pin "1") (pinfunction "1_1") (pintype "passive"))
      (node (ref "R35") (pin "1") (pinfunction "1_1") (pintype "passive"))
      (node (ref "R39") (pin "1") (pinfunction "1_1") (pintype "passive"))
      (node (ref "R40") (pin "1") (pinfunction "1_1") (pintype "passive"))
    )
    (net (code "7") (name "GND") (class "Default")
      (node (ref "C10") (pin "1") (pinfunction "1_1") (pintype "passive"))
      (node (ref "C13") (pin "1") (pinfunction "1_1") (pintype "passive"))
      (node (ref "C14") (pin "1") (pinfunction "1_1") (pintype "passive"))
      (node (ref "C15") (pin "1") (pinfunction "1_1") (pintype "passive"))
      (node (ref "C16") (pin "1") (pinfunction "1_1") (pintype "passive"))
      (node (ref "C17") (pin "1") (pinfunction "1_1") (pintype "passive"))
      (node (ref "C21") (pin "1") (pinfunction "1_1") (pintype "passive"))
      (node (ref "D2") (pin "1") (pinfunction "1_1") (pintype "passive"))
      (node (ref "D3") (pin "1") (pinfunction "1_1") (pintype "passive"))
      (node (ref "D4") (pin "1") (pinfunction "1_1") (pintype "passive"))
      (node (ref "J1") (pin "1") (pinfunction "1_1") (pintype "passive"))
      (node (ref "J1") (pin "6") (pinfunction "6_6") (pintype "passive"))
      (node (ref "J1") (pin "7") (pinfunction "7_7") (pintype "passive"))
      (node (ref "J2") (pin "2") (pinfunction "PACK-_2") (pintype "passive"))
      (node (ref "J2") (pin "3") (pinfunction "PACK-_3") (pintype "passive"))
      (node (ref "J2") (pin "8") (pinfunction "PACK-_8") (pintype "passive"))
      (node (ref "J2") (pin "9") (pinfunction "PACK-_9") (pintype "passive"))
      (node (ref "Q5") (pin "2") (pinfunction "S_2") (pintype "passive"))
      (node (ref "R16") (pin "1") (pinfunction "1_1") (pintype "passive"))
      (node (ref "R17") (pin "2") (pinfunction "2_2") (pintype "passive"))
      (node (ref "R19") (pin "1") (pinfunction "1_1") (pintype "passive"))
      (node (ref "R19") (pin "2") (pinfunction "2_2") (pintype "passive"))
      (node (ref "R23") (pin "1") (pinfunction "1_1") (pintype "passive"))
      (node (ref "R30") (pin "1") (pinfunction "1_1") (pintype "passive"))
      (node (ref "R31") (pin "1") (pinfunction "1_1") (pintype "passive"))
      (node (ref "R4") (pin "1") (pinfunction "1_1") (pintype "passive"))
      (node (ref "R4") (pin "2") (pinfunction "2_2") (pintype "passive"))
      (node (ref "RT2") (pin "1") (pinfunction "1_1") (pintype "passive"))
      (node (ref "S2") (pin "3") (pinfunction "3_3") (pintype "passive"))
      (node (ref "S2") (pin "4") (pinfunction "4_4") (pintype "passive"))
      (node (ref "S3") (pin "3") (pinfunction "3_3") (pintype "passive"))
      (node (ref "S3") (pin "4") (pinfunction "4_4") (pintype "passive"))
      (node (ref "U1") (pin "11") (pinfunction "TS2_11") (pintype "passive"))
      (node (ref "U1") (pin "12") (pinfunction "TS3_12") (pintype "passive"))
      (node (ref "U1") (pin "13") (pinfunction "TS4_13") (pintype "passive"))
      (node (ref "U1") (pin "14") (pinfunction "NC_14") (pintype "passive"))
      (node (ref "U1") (pin "23") (pinfunction "PTC_23") (pintype "passive"))
      (node (ref "U1") (pin "24") (pinfunction "PTCEN_24") (pintype "passive"))
      (node (ref "U1") (pin "29") (pinfunction "NC_29") (pintype "passive"))
      (node (ref "U1") (pin "33") (pinfunction "PWPD_33") (pintype "passive"))
      (node (ref "U1") (pin "7") (pinfunction "NC_7") (pintype "passive"))
      (node (ref "U1") (pin "9") (pinfunction "VSS_9") (pintype "passive"))
    )
    (net (code "8") (name "Net-(C1-Pad1)") (class "Default")
      (node (ref "C1") (pin "1") (pinfunction "1_1") (pintype "passive"))
      (node (ref "C2") (pin "2") (pinfunction "2_2") (pintype "passive"))
    )
    (net (code "9") (name "Net-(C5-Pad2)") (class "Default")
      (node (ref "C5") (pin "2") (pinfunction "2_2") (pintype "passive"))
      (node (ref "R6") (pin "1") (pinfunction "1_1") (pintype "passive"))
    )
    (net (code "10") (name "Net-(C7-Pad2)") (class "Default")
      (node (ref "C7") (pin "2") (pinfunction "2_2") (pintype "passive"))
      (node (ref "R18") (pin "2") (pinfunction "2_2") (pintype "passive"))
      (node (ref "R26") (pin "2") (pinfunction "2_2") (pintype "passive"))
    )
    (net (code "11") (name "Net-(C10-Pad2)") (class "Default")
      (node (ref "C10") (pin "2") (pinfunction "2_2") (pintype "passive"))
      (node (ref "C8") (pin "1") (pinfunction "1_1") (pintype "passive"))
    )
    (net (code "12") (name "Net-(C19-Pad2)") (class "Default")
      (node (ref "C19") (pin "2") (pinfunction "2_2") (pintype "passive"))
      (node (ref "C22") (pin "2") (pinfunction "2_2") (pintype "passive"))
      (node (ref "L1") (pin "2") (pinfunction "2_2") (pintype "passive"))
      (node (ref "R24") (pin "1") (pinfunction "1_1") (pintype "passive"))
    )
    (net (code "13") (name "Net-(C23-Pad2)") (class "Default")
      (node (ref "C23") (pin "2") (pinfunction "2_2") (pintype "passive"))
      (node (ref "R33") (pin "1") (pinfunction "1_1") (pintype "passive"))
    )
    (net (code "14") (name "Net-(C24-Pad2)") (class "Default")
      (node (ref "C24") (pin "2") (pinfunction "2_2") (pintype "passive"))
      (node (ref "R38") (pin "2") (pinfunction "2_2") (pintype "passive"))
    )
    (net (code "15") (name "Net-(D4-Pad2)") (class "Default")
      (node (ref "D4") (pin "2") (pinfunction "2_2") (pintype "passive"))
      (node (ref "R28") (pin "2") (pinfunction "2_2") (pintype "passive"))
    )
    (net (code "16") (name "Net-(D5-A)") (class "Default")
      (node (ref "D5") (pin "2") (pinfunction "A_2") (pintype "passive"))
      (node (ref "D6") (pin "1") (pinfunction "C_1") (pintype "passive"))
      (node (ref "D7") (pin "1") (pinfunction "C_1") (pintype "passive"))
      (node (ref "D8") (pin "2") (pinfunction "A_2") (pintype "passive"))
      (node (ref "U1") (pin "21") (pinfunction "LEDCNTLB_21") (pintype "passive"))
    )
    (net (code "17") (name "Net-(D5-C)") (class "Default")
      (node (ref "D5") (pin "1") (pinfunction "C_1") (pintype "passive"))
      (node (ref "D6") (pin "2") (pinfunction "A_2") (pintype "passive"))
      (node (ref "D9") (pin "2") (pinfunction "A_2") (pintype "passive"))
      (node (ref "U1") (pin "22") (pinfunction "LEDCNTLC_22") (pintype "passive"))
    )
    (net (code "18") (name "Net-(D7-A)") (class "Default")
      (node (ref "D7") (pin "2") (pinfunction "A_2") (pintype "passive"))
      (node (ref "D8") (pin "1") (pinfunction "C_1") (pintype "passive"))
      (node (ref "D9") (pin "1") (pinfunction "C_1") (pintype "passive"))
      (node (ref "U1") (pin "20") (pinfunction "LEDCNTLA_20") (pintype "passive"))
    )
    (net (code "19") (name "Net-(D10-A)") (class "Default")
      (node (ref "C20") (pin "2") (pinfunction "2_2") (pintype "passive"))
      (node (ref "D10") (pin "2") (pinfunction "A_2") (pintype "passive"))
      (node (ref "Q10") (pin "4") (pinfunction "G_4") (pintype "passive"))
    )
    (net (code "20") (name "Net-(D10-C)") (class "Default")
      (node (ref "C6") (pin "2") (pinfunction "2_2") (pintype "passive"))
      (node (ref "D10") (pin "1") (pinfunction "C_1") (pintype "passive"))
    )
    (net (code "21") (name "Net-(D11-A)") (class "Default")
      (node (ref "D11") (pin "1") (pinfunction "A_1") (pintype "passive"))
      (node (ref "J3") (pin "A4B9") (pinfunction "VBUS_A4B9") (pintype "passive"))
      (node (ref "J3") (pin "B4A9") (pinfunction "VBUS_B4A9") (pintype "passive"))
      (node (ref "R6") (pin "2") (pinfunction "2_2") (pintype "passive"))
    )
    (net (code "22") (name "Net-(D11-K)") (class "Default")
      (node (ref "C3") (pin "2") (pinfunction "2_2") (pintype "passive"))
      (node (ref "C4") (pin "2") (pinfunction "2_2") (pintype "passive"))
      (node (ref "D11") (pin "2") (pinfunction "K_2") (pintype "passive"))
      (node (ref "Q8") (pin "5") (pinfunction "D_5") (pintype "passive"))
      (node (ref "R33") (pin "2") (pinfunction "2_2") (pintype "passive"))
      (node (ref "R36") (pin "2") (pinfunction "2_2") (pintype "passive"))
      (node (ref "R37") (pin "2") (pinfunction "2_2") (pintype "passive"))
    )
    (net (code "23") (name "Net-(D12-A)") (class "Default")
      (node (ref "D12") (pin "2") (pinfunction "A_2") (pintype "passive"))
      (node (ref "R36") (pin "1") (pinfunction "1_1") (pintype "passive"))
    )
    (net (code "24") (name "Net-(D13-A)") (class "Default")
      (node (ref "D13") (pin "2") (pinfunction "A_2") (pintype "passive"))
      (node (ref "R37") (pin "1") (pinfunction "1_1") (pintype "passive"))
    )
    (net (code "25") (name "Net-(Q1-D-Pad5)") (class "Default")
      (node (ref "Q1") (pin "5") (pinfunction "D_5") (pintype "passive"))
      (node (ref "Q1") (pin "6") (pinfunction "D_6") (pintype "passive"))
      (node (ref "Q1") (pin "7") (pinfunction "D_7") (pintype "passive"))
      (node (ref "Q1") (pin "8") (pinfunction "D_8") (pintype "passive"))
      (node (ref "Q1") (pin "9") (pinfunction "D_9") (pintype "passive"))
      (node (ref "R1") (pin "2") (pinfunction "2_2") (pintype "passive"))
    )
    (net (code "26") (name "Net-(Q1-G)") (class "Default")
      (node (ref "Q1") (pin "4") (pinfunction "G_4") (pintype "passive"))
      (node (ref "R5") (pin "1") (pinfunction "1_1") (pintype "passive"))
      (node (ref "R8") (pin "2") (pinfunction "2_2") (pintype "passive"))
    )
    (net (code "27") (name "Net-(Q2-D)") (class "Default")
      (node (ref "Q2") (pin "3") (pinfunction "D_3") (pintype "passive"))
      (node (ref "R11") (pin "2") (pinfunction "2_2") (pintype "passive"))
    )
    (net (code "28") (name "Net-(Q2-G)") (class "Default")
      (node (ref "C14") (pin "2") (pinfunction "2_2") (pintype "passive"))
      (node (ref "Q2") (pin "1") (pinfunction "G_1") (pintype "passive"))
      (node (ref "R13") (pin "2") (pinfunction "2_2") (pintype "passive"))
      (node (ref "U1") (pin "2") (pinfunction "VC4_2") (pintype "passive"))
    )
    (net (code "29") (name "Net-(Q2-S)") (class "Default")
      (node (ref "J1") (pin "4") (pinfunction "4_4") (pintype "passive"))
      (node (ref "Q2") (pin "2") (pinfunction "S_2") (pintype "passive"))
      (node (ref "R13") (pin "1") (pinfunction "1_1") (pintype "passive"))
      (node (ref "R14") (pin "1") (pinfunction "1_1") (pintype "passive"))
    )
    (net (code "30") (name "Net-(Q3-D)") (class "Default")
      (node (ref "Q3") (pin "3") (pinfunction "D_3") (pintype "passive"))
      (node (ref "R14") (pin "2") (pinfunction "2_2") (pintype "passive"))
    )
    (net (code "31") (name "Net-(Q3-G)") (class "Default")
      (node (ref "C15") (pin "2") (pinfunction "2_2") (pintype "passive"))
      (node (ref "Q3") (pin "1") (pinfunction "G_1") (pintype "passive"))
      (node (ref "R21") (pin "1") (pinfunction "1_1") (pintype "passive"))
      (node (ref "U1") (pin "3") (pinfunction "VC3_3") (pintype "passive"))
    )
    (net (code "32") (name "Net-(Q3-S)") (class "Default")
      (node (ref "J1") (pin "3") (pinfunction "3_3") (pintype "passive"))
      (node (ref "Q3") (pin "2") (pinfunction "S_2") (pintype "passive"))
      (node (ref "R20") (pin "2") (pinfunction "2_2") (pintype "passive"))
      (node (ref "R21") (pin "2") (pinfunction "2_2") (pintype "passive"))
    )
    (net (code "33") (name "Net-(Q4-D)") (class "Default")
      (node (ref "Q4") (pin "3") (pinfunction "D_3") (pintype "passive"))
      (node (ref "R20") (pin "1") (pinfunction "1_1") (pintype "passive"))
    )
    (net (code "34") (name "Net-(Q4-G)") (class "Default")
      (node (ref "C16") (pin "2") (pinfunction "2_2") (pintype "passive"))
      (node (ref "Q4") (pin "1") (pinfunction "G_1") (pintype "passive"))
      (node (ref "R22") (pin "2") (pinfunction "2_2") (pintype "passive"))
      (node (ref "U1") (pin "4") (pinfunction "VC2_4") (pintype "passive"))
    )
    (net (code "35") (name "Net-(Q4-S)") (class "Default")
      (node (ref "J1") (pin "2") (pinfunction "2_2") (pintype "passive"))
      (node (ref "Q4") (pin "2") (pinfunction "S_2") (pintype "passive"))
      (node (ref "R15") (pin "2") (pinfunction "2_2") (pintype "passive"))
      (node (ref "R22") (pin "1") (pinfunction "1_1") (pintype "passive"))
    )
    (net (code "36") (name "Net-(Q5-D)") (class "Default")
      (node (ref "Q5") (pin "3") (pinfunction "D_3") (pintype "passive"))
      (node (ref "R15") (pin "1") (pinfunction "1_1") (pintype "passive"))
    )
    (net (code "37") (name "Net-(Q5-G)") (class "Default")
      (node (ref "C17") (pin "2") (pinfunction "2_2") (pintype "passive"))
      (node (ref "Q5") (pin "1") (pinfunction "G_1") (pintype "passive"))
      (node (ref "R23") (pin "2") (pinfunction "2_2") (pintype "passive"))
      (node (ref "U1") (pin "5") (pinfunction "VC1_5") (pintype "passive"))
    )
    (net (code "38") (name "Net-(Q6-D)") (class "Default")
      (node (ref "Q1") (pin "1") (pinfunction "S_1") (pintype "passive"))
      (node (ref "Q1") (pin "2") (pinfunction "S_2") (pintype "passive"))
      (node (ref "Q1") (pin "3") (pinfunction "S_3") (pintype "passive"))
      (node (ref "Q6") (pin "5") (pinfunction "D_5") (pintype "passive"))
      (node (ref "Q7") (pin "5") (pinfunction "D_5") (pintype "passive"))
      (node (ref "R5") (pin "2") (pinfunction "2_2") (pintype "passive"))
      (node (ref "R9") (pin "2") (pinfunction "2_2") (pintype "passive"))
    )
    (net (code "39") (name "Net-(Q6-G)") (class "Default")
      (node (ref "Q6") (pin "4") (pinfunction "G_4") (pintype "passive"))
      (node (ref "Q9") (pin "3") (pinfunction "D_3") (pintype "passive"))
      (node (ref "R10") (pin "2") (pinfunction "2_2") (pintype "passive"))
      (node (ref "R3") (pin "1") (pinfunction "1_1") (pintype "passive"))
    )
    (net (code "40") (name "Net-(Q7-G)") (class "Default")
      (node (ref "Q7") (pin "4") (pinfunction "G_4") (pintype "passive"))
      (node (ref "R2") (pin "1") (pinfunction "1_1") (pintype "passive"))
      (node (ref "R7") (pin "2") (pinfunction "2_2") (pintype "passive"))
    )
    (net (code "41") (name "Net-(Q9-G)") (class "Default")
      (node (ref "Q9") (pin "1") (pinfunction "G_1") (pintype "passive"))
      (node (ref "R16") (pin "2") (pinfunction "2_2") (pintype "passive"))
    )
    (net (code "42") (name "Net-(Q10-D)") (class "Default")
      (node (ref "C6") (pin "1") (pinfunction "1_1") (pintype "passive"))
      (node (ref "L1") (pin "1") (pinfunction "1_1") (pintype "passive"))
      (node (ref "Q10") (pin "5") (pinfunction "D_5") (pintype "passive"))
      (node (ref "Q8") (pin "1") (pinfunction "S_1") (pintype "passive"))
      (node (ref "Q8") (pin "2") (pinfunction "S_2") (pintype "passive"))
      (node (ref "Q8") (pin "3") (pinfunction "S_3") (pintype "passive"))
    )
    (net (code "43") (name "Net-(R18-Pad1)") (class "Default")
      (node (ref "R18") (pin "1") (pinfunction "1_1") (pintype "passive"))
      (node (ref "R38") (pin "1") (pinfunction "1_1") (pintype "passive"))
      (node (ref "R39") (pin "2") (pinfunction "2_2") (pintype "passive"))
      (node (ref "R40") (pin "2") (pinfunction "2_2") (pintype "passive"))
    )
    (net (code "44") (name "Net-(R26-Pad1)") (class "Default")
      (node (ref "R26") (pin "1") (pinfunction "1_1") (pintype "passive"))
      (node (ref "R32") (pin "2") (pinfunction "2_2") (pintype "passive"))
    )
    (net (code "45") (name "Net-(R29-Pad1)") (class "Default")
      (node (ref "R29") (pin "1") (pinfunction "1_1") (pintype "passive"))
      (node (ref "R34") (pin "2") (pinfunction "2_2") (pintype "passive"))
    )
    (net (code "46") (name "Net-(R34-Pad1)") (class "Default")
      (node (ref "R34") (pin "1") (pinfunction "1_1") (pintype "passive"))
      (node (ref "R35") (pin "2") (pinfunction "2_2") (pintype "passive"))
    )
    (net (code "47") (name "Net-(U1-BTP_INT)") (class "Default")
      (node (ref "TP12") (pin "1") (pinfunction "1_1") (pintype "passive"))
      (node (ref "U1") (pin "15") (pinfunction "BTP_INT_15") (pintype "passive"))
    )
    (net (code "48") (name "Net-(U1-CHG)") (class "Default")
      (node (ref "R7") (pin "1") (pinfunction "1_1") (pintype "passive"))
      (node (ref "TP5") (pin "1") (pinfunction "1_1") (pintype "passive"))
      (node (ref "U1") (pin "31") (pinfunction "CHG_31") (pintype "passive"))
    )
    (net (code "49") (name "Net-(U1-DISP)") (class "Default")
      (node (ref "S2") (pin "1") (pinfunction "1_1") (pintype "passive"))
      (node (ref "S2") (pin "2") (pinfunction "2_2") (pintype "passive"))
      (node (ref "U1") (pin "17") (pinfunction "DISP_17") (pintype "passive"))
    )
    (net (code "50") (name "Net-(U1-DSG)") (class "Default")
      (node (ref "R10") (pin "1") (pinfunction "1_1") (pintype "passive"))
      (node (ref "TP6") (pin "1") (pinfunction "1_1") (pintype "passive"))
      (node (ref "U1") (pin "28") (pinfunction "DSG_28") (pintype "passive"))
    )
    (net (code "51") (name "Net-(U1-FUSE)") (class "Default")
      (node (ref "R17") (pin "1") (pinfunction "1_1") (pintype "passive"))
      (node (ref "U1") (pin "25") (pinfunction "FUSE_25") (pintype "passive"))
    )
    (net (code "52") (name "Net-(U1-PACK)") (class "Default")
      (node (ref "R12") (pin "1") (pinfunction "1_1") (pintype "passive"))
      (node (ref "U1") (pin "27") (pinfunction "PACK_27") (pintype "passive"))
    )
    (net (code "53") (name "Net-(U1-PBI)") (class "Default")
      (node (ref "C13") (pin "2") (pinfunction "2_2") (pintype "passive"))
      (node (ref "U1") (pin "1") (pinfunction "PBI_1") (pintype "passive"))
    )
    (net (code "54") (name "Net-(U1-PCHG)") (class "Default")
      (node (ref "R8") (pin "1") (pinfunction "1_1") (pintype "passive"))
      (node (ref "U1") (pin "30") (pinfunction "PCHG_30") (pintype "passive"))
    )
    (net (code "55") (name "Net-(U1-PRESorSHUTDN)") (class "Default")
      (node (ref "C21") (pin "2") (pinfunction "2_2") (pintype "passive"))
      (node (ref "R28") (pin "1") (pinfunction "1_1") (pintype "passive"))
      (node (ref "S3") (pin "1") (pinfunction "1_1") (pintype "passive"))
      (node (ref "S3") (pin "2") (pinfunction "2_2") (pintype "passive"))
      (node (ref "U1") (pin "16") (pinfunction "PRESorSHUTDN_16") (pintype "passive"))
    )
    (net (code "56") (name "Net-(U1-SMBC)") (class "Default")
      (node (ref "D2") (pin "2") (pinfunction "2_2") (pintype "passive"))
      (node (ref "R25") (pin "1") (pinfunction "1_1") (pintype "passive"))
      (node (ref "U1") (pin "19") (pinfunction "SMBC_19") (pintype "passive"))
    )
    (net (code "57") (name "Net-(U1-SMBD)") (class "Default")
      (node (ref "D3") (pin "2") (pinfunction "2_2") (pintype "passive"))
      (node (ref "R27") (pin "1") (pinfunction "1_1") (pintype "passive"))
      (node (ref "U1") (pin "18") (pinfunction "SMBD_18") (pintype "passive"))
    )
    (net (code "58") (name "Net-(U1-SRN)") (class "Default")
      (node (ref "C18") (pin "1") (pinfunction "1_1") (pintype "passive"))
      (node (ref "R31") (pin "2") (pinfunction "2_2") (pintype "passive"))
      (node (ref "TP2") (pin "1") (pinfunction "1_1") (pintype "passive"))
      (node (ref "U1") (pin "6") (pinfunction "SRN_6") (pintype "passive"))
    )
    (net (code "59") (name "Net-(U1-SRP)") (class "Default")
      (node (ref "C18") (pin "2") (pinfunction "2_2") (pintype "passive"))
      (node (ref "R30") (pin "2") (pinfunction "2_2") (pintype "passive"))
      (node (ref "TP1") (pin "1") (pinfunction "1_1") (pintype "passive"))
      (node (ref "U1") (pin "8") (pinfunction "SRP_8") (pintype "passive"))
    )
    (net (code "60") (name "Net-(U1-TS1)") (class "Default")
      (node (ref "RT2") (pin "2") (pinfunction "2_2") (pintype "passive"))
      (node (ref "U1") (pin "10") (pinfunction "TS1_10") (pintype "passive"))
    )
    (net (code "61") (name "Net-(U1-VCC)") (class "Default")
      (node (ref "R9") (pin "1") (pinfunction "1_1") (pintype "passive"))
      (node (ref "U1") (pin "26") (pinfunction "VCC_26") (pintype "passive"))
    )
    (net (code "62") (name "unconnected-(C5-Pad1)") (class "Default")
      (node (ref "C5") (pin "1") (pinfunction "1_1") (pintype "passive"))
    )
    (net (code "63") (name "unconnected-(D12-C-Pad1)") (class "Default")
      (node (ref "D12") (pin "1") (pinfunction "C_1") (pintype "passive"))
    )
    (net (code "64") (name "unconnected-(D13-C-Pad1)") (class "Default")
      (node (ref "D13") (pin "1") (pinfunction "C_1") (pintype "passive"))
    )
    (net (code "65") (name "unconnected-(J3-CC1-PadA5)") (class "Default")
      (node (ref "J3") (pin "A5") (pinfunction "CC1_A5") (pintype "passive"))
    )
    (net (code "66") (name "unconnected-(J3-CC2-PadB5)") (class "Default")
      (node (ref "J3") (pin "B5") (pinfunction "CC2_B5") (pintype "passive"))
    )
    (net (code "67") (name "unconnected-(J3-DN1-PadA7)") (class "Default")
      (node (ref "J3") (pin "A7") (pinfunction "DN1_A7") (pintype "passive"))
    )
    (net (code "68") (name "unconnected-(J3-DN2-PadB7)") (class "Default")
      (node (ref "J3") (pin "B7") (pinfunction "DN2_B7") (pintype "passive"))
    )
    (net (code "69") (name "unconnected-(J3-DP1-PadA6)") (class "Default")
      (node (ref "J3") (pin "A6") (pinfunction "DP1_A6") (pintype "passive"))
    )
    (net (code "70") (name "unconnected-(J3-DP2-PadB6)") (class "Default")
      (node (ref "J3") (pin "B6") (pinfunction "DP2_B6") (pintype "passive"))
    )
    (net (code "71") (name "unconnected-(J3-SBU1-PadA8)") (class "Default")
      (node (ref "J3") (pin "A8") (pinfunction "SBU1_A8") (pintype "passive"))
    )
    (net (code "72") (name "unconnected-(J3-SBU2-PadB8)") (class "Default")
      (node (ref "J3") (pin "B8") (pinfunction "SBU2_B8") (pintype "passive"))
    )
    (net (code "73") (name "unconnected-(J3-SHELL-Pad1)") (class "Default")
      (node (ref "J3") (pin "1") (pinfunction "SHELL_1") (pintype "passive"))
    )
    (net (code "74") (name "unconnected-(J3-SHELL-Pad2)") (class "Default")
      (node (ref "J3") (pin "2") (pinfunction "SHELL_2") (pintype "passive"))
    )
    (net (code "75") (name "unconnected-(J3-SHELL-Pad3)") (class "Default")
      (node (ref "J3") (pin "3") (pinfunction "SHELL_3") (pintype "passive"))
    )
    (net (code "76") (name "unconnected-(J3-SHELL-Pad4)") (class "Default")
      (node (ref "J3") (pin "4") (pinfunction "SHELL_4") (pintype "passive"))
    )
    (net (code "77") (name "unconnected-(J4-D+-Pad4)") (class "Default")
      (node (ref "J4") (pin "4") (pinfunction "D+_4") (pintype "passive"))
    )
    (net (code "78") (name "unconnected-(J4-D--Pad2)") (class "Default")
      (node (ref "J4") (pin "2") (pinfunction "D-_2") (pintype "passive"))
    )
    (net (code "79") (name "unconnected-(J4-GND-Pad5)") (class "Default")
      (node (ref "J4") (pin "5") (pinfunction "GND_5") (pintype "passive"))
    )
    (net (code "80") (name "unconnected-(J4-ID-Pad3)") (class "Default")
      (node (ref "J4") (pin "3") (pinfunction "ID_3") (pintype "passive"))
    )
    (net (code "81") (name "unconnected-(J4-Pad6)") (class "Default")
      (node (ref "J4") (pin "6") (pinfunction "6_6") (pintype "passive"))
    )
    (net (code "82") (name "unconnected-(J4-Pad7)") (class "Default")
      (node (ref "J4") (pin "7") (pinfunction "7_7") (pintype "passive"))
    )
    (net (code "83") (name "unconnected-(J4-Pad8)") (class "Default")
      (node (ref "J4") (pin "8") (pinfunction "8_8") (pintype "passive"))
    )
    (net (code "84") (name "unconnected-(J4-Pad9)") (class "Default")
      (node (ref "J4") (pin "9") (pinfunction "9_9") (pintype "passive"))
    )
    (net (code "85") (name "unconnected-(J4-VCC-Pad1)") (class "Default")
      (node (ref "J4") (pin "1") (pinfunction "VCC_1") (pintype "passive"))
    )
    (net (code "86") (name "unconnected-(Q8-G-Pad4)") (class "Default")
      (node (ref "Q8") (pin "4") (pinfunction "G_4") (pintype "passive"))
    )
    (net (code "87") (name "unconnected-(Q11-D-Pad5)") (class "Default")
      (node (ref "Q11") (pin "5") (pinfunction "D_5") (pintype "passive"))
    )
    (net (code "88") (name "unconnected-(Q11-G-Pad4)") (class "Default")
      (node (ref "Q11") (pin "4") (pinfunction "G_4") (pintype "passive"))
    )
    (net (code "89") (name "unconnected-(Q11-S-Pad1)") (class "Default")
      (node (ref "Q11") (pin "1") (pinfunction "S_1") (pintype "passive"))
    )
    (net (code "90") (name "unconnected-(Q11-S-Pad2)") (class "Default")
      (node (ref "Q11") (pin "2") (pinfunction "S_2") (pintype "passive"))
    )
    (net (code "91") (name "unconnected-(Q11-S-Pad3)") (class "Default")
      (node (ref "Q11") (pin "3") (pinfunction "S_3") (pintype "passive"))
    )
    (net (code "92") (name "unconnected-(Q12-D-Pad5)") (class "Default")
      (node (ref "Q12") (pin "5") (pinfunction "D_5") (pintype "passive"))
    )
    (net (code "93") (name "unconnected-(Q12-G-Pad4)") (class "Default")
      (node (ref "Q12") (pin "4") (pinfunction "G_4") (pintype "passive"))
    )
    (net (code "94") (name "unconnected-(Q12-S-Pad1)") (class "Default")
      (node (ref "Q12") (pin "1") (pinfunction "S_1") (pintype "passive"))
    )
    (net (code "95") (name "unconnected-(Q12-S-Pad2)") (class "Default")
      (node (ref "Q12") (pin "2") (pinfunction "S_2") (pintype "passive"))
    )
    (net (code "96") (name "unconnected-(Q12-S-Pad3)") (class "Default")
      (node (ref "Q12") (pin "3") (pinfunction "S_3") (pintype "passive"))
    )
    (net (code "97") (name "unconnected-(Q13-D-Pad5)") (class "Default")
      (node (ref "Q13") (pin "5") (pinfunction "D_5") (pintype "passive"))
    )
    (net (code "98") (name "unconnected-(Q13-D-Pad6)") (class "Default")
      (node (ref "Q13") (pin "6") (pinfunction "D_6") (pintype "passive"))
    )
    (net (code "99") (name "unconnected-(Q13-D-Pad7)") (class "Default")
      (node (ref "Q13") (pin "7") (pinfunction "D_7") (pintype "passive"))
    )
    (net (code "100") (name "unconnected-(Q13-D-Pad8)") (class "Default")
      (node (ref "Q13") (pin "8") (pinfunction "D_8") (pintype "passive"))
    )
    (net (code "101") (name "unconnected-(Q13-D-Pad9)") (class "Default")
      (node (ref "Q13") (pin "9") (pinfunction "D_9") (pintype "passive"))
    )
    (net (code "102") (name "unconnected-(Q13-G-Pad4)") (class "Default")
      (node (ref "Q13") (pin "4") (pinfunction "G_4") (pintype "passive"))
    )
    (net (code "103") (name "unconnected-(Q13-S-Pad1)") (class "Default")
      (node (ref "Q13") (pin "1") (pinfunction "S_1") (pintype "passive"))
    )
    (net (code "104") (name "unconnected-(Q13-S-Pad2)") (class "Default")
      (node (ref "Q13") (pin "2") (pinfunction "S_2") (pintype "passive"))
    )
    (net (code "105") (name "unconnected-(Q13-S-Pad3)") (class "Default")
      (node (ref "Q13") (pin "3") (pinfunction "S_3") (pintype "passive"))
    )
    (net (code "106") (name "unconnected-(Q14-D-Pad3)") (class "Default")
      (node (ref "Q14") (pin "3") (pinfunction "D_3") (pintype "passive"))
    )
    (net (code "107") (name "unconnected-(Q14-G-Pad1)") (class "Default")
      (node (ref "Q14") (pin "1") (pinfunction "G_1") (pintype "passive"))
    )
    (net (code "108") (name "unconnected-(Q14-S-Pad2)") (class "Default")
      (node (ref "Q14") (pin "2") (pinfunction "S_2") (pintype "passive"))
    )
    (net (code "109") (name "unconnected-(Q15-D-Pad3)") (class "Default")
      (node (ref "Q15") (pin "3") (pinfunction "D_3") (pintype "passive"))
    )
    (net (code "110") (name "unconnected-(Q15-G-Pad1)") (class "Default")
      (node (ref "Q15") (pin "1") (pinfunction "G_1") (pintype "passive"))
    )
    (net (code "111") (name "unconnected-(Q15-S-Pad2)") (class "Default")
      (node (ref "Q15") (pin "2") (pinfunction "S_2") (pintype "passive"))
    )
    (net (code "112") (name "unconnected-(Q16-D-Pad3)") (class "Default")
      (node (ref "Q16") (pin "3") (pinfunction "D_3") (pintype "passive"))
    )
    (net (code "113") (name "unconnected-(Q16-G-Pad1)") (class "Default")
      (node (ref "Q16") (pin "1") (pinfunction "G_1") (pintype "passive"))
    )
    (net (code "114") (name "unconnected-(Q16-S-Pad2)") (class "Default")
      (node (ref "Q16") (pin "2") (pinfunction "S_2") (pintype "passive"))
    )
    (net (code "115") (name "unconnected-(Q17-D-Pad3)") (class "Default")
      (node (ref "Q17") (pin "3") (pinfunction "D_3") (pintype "passive"))
    )
    (net (code "116") (name "unconnected-(Q17-G-Pad1)") (class "Default")
      (node (ref "Q17") (pin "1") (pinfunction "G_1") (pintype "passive"))
    )
    (net (code "117") (name "unconnected-(Q17-S-Pad2)") (class "Default")
      (node (ref "Q17") (pin "2") (pinfunction "S_2") (pintype "passive"))
    )
    (net (code "118") (name "unconnected-(U2-PA0-Pad11)") (class "Default")
      (node (ref "U2") (pin "11") (pinfunction "PA0_11") (pintype "passive"))
    )
    (net (code "119") (name "unconnected-(U2-PA1-Pad12)") (class "Default")
      (node (ref "U2") (pin "12") (pinfunction "PA1_12") (pintype "passive"))
    )
    (net (code "120") (name "unconnected-(U2-PA2-Pad13)") (class "Default")
      (node (ref "U2") (pin "13") (pinfunction "PA2_13") (pintype "passive"))
    )
    (net (code "121") (name "unconnected-(U2-PA3-Pad14)") (class "Default")
      (node (ref "U2") (pin "14") (pinfunction "PA3_14") (pintype "passive"))
    )
    (net (code "122") (name "unconnected-(U2-PA4-Pad15)") (class "Default")
      (node (ref "U2") (pin "15") (pinfunction "PA4_15") (pintype "passive"))
    )
    (net (code "123") (name "unconnected-(U2-PA5-Pad16)") (class "Default")
      (node (ref "U2") (pin "16") (pinfunction "PA5_16") (pintype "passive"))
    )
    (net (code "124") (name "unconnected-(U2-PA6-Pad17)") (class "Default")
      (node (ref "U2") (pin "17") (pinfunction "PA6_17") (pintype "passive"))
    )
    (net (code "125") (name "unconnected-(U2-PA7-Pad18)") (class "Default")
      (node (ref "U2") (pin "18") (pinfunction "PA7_18") (pintype "passive"))
    )
    (net (code "126") (name "unconnected-(U2-PA8-Pad28)") (class "Default")
      (node (ref "U2") (pin "28") (pinfunction "PA8_28") (pintype "passive"))
    )
    (net (code "127") (name "unconnected-(U2-PA9-Pad29)") (class "Default")
      (node (ref "U2") (pin "29") (pinfunction "PA9_29") (pintype "passive"))
    )
    (net (code "128") (name "unconnected-(U2-PA10-Pad32)") (class "Default")
      (node (ref "U2") (pin "32") (pinfunction "PA10_32") (pintype "passive"))
    )
    (net (code "129") (name "unconnected-(U2-PA11[PA9]-Pad33)") (class "Default")
      (node (ref "U2") (pin "33") (pinfunction "PA11[PA9]_33") (pintype "passive"))
    )
    (net (code "130") (name "unconnected-(U2-PA12[PA10]-Pad34)") (class "Default")
      (node (ref "U2") (pin "34") (pinfunction "PA12[PA10]_34") (pintype "passive"))
    )
    (net (code "131") (name "unconnected-(U2-PA13-Pad35)") (class "Default")
      (node (ref "U2") (pin "35") (pinfunction "PA13_35") (pintype "passive"))
    )
    (net (code "132") (name "unconnected-(U2-PA14-BOOT0-Pad36)") (class "Default")
      (node (ref "U2") (pin "36") (pinfunction "PA14-BOOT0_36") (pintype "passive"))
    )
    (net (code "133") (name "unconnected-(U2-PA15-Pad37)") (class "Default")
      (node (ref "U2") (pin "37") (pinfunction "PA15_37") (pintype "passive"))
    )
    (net (code "134") (name "unconnected-(U2-PB0-Pad19)") (class "Default")
      (node (ref "U2") (pin "19") (pinfunction "PB0_19") (pintype "passive"))
    )
    (net (code "135") (name "unconnected-(U2-PB1-Pad20)") (class "Default")
      (node (ref "U2") (pin "20") (pinfunction "PB1_20") (pintype "passive"))
    )
    (net (code "136") (name "unconnected-(U2-PB2-Pad21)") (class "Default")
      (node (ref "U2") (pin "21") (pinfunction "PB2_21") (pintype "passive"))
    )
    (net (code "137") (name "unconnected-(U2-PB3-Pad42)") (class "Default")
      (node (ref "U2") (pin "42") (pinfunction "PB3_42") (pintype "passive"))
    )
    (net (code "138") (name "unconnected-(U2-PB4-Pad43)") (class "Default")
      (node (ref "U2") (pin "43") (pinfunction "PB4_43") (pintype "passive"))
    )
    (net (code "139") (name "unconnected-(U2-PB5-Pad44)") (class "Default")
      (node (ref "U2") (pin "44") (pinfunction "PB5_44") (pintype "passive"))
    )
    (net (code "140") (name "unconnected-(U2-PB6-Pad45)") (class "Default")
      (node (ref "U2") (pin "45") (pinfunction "PB6_45") (pintype "passive"))
    )
    (net (code "141") (name "unconnected-(U2-PB7-Pad46)") (class "Default")
      (node (ref "U2") (pin "46") (pinfunction "PB7_46") (pintype "passive"))
    )
    (net (code "142") (name "unconnected-(U2-PB8-Pad47)") (class "Default")
      (node (ref "U2") (pin "47") (pinfunction "PB8_47") (pintype "passive"))
    )
    (net (code "143") (name "unconnected-(U2-PB9-Pad48)") (class "Default")
      (node (ref "U2") (pin "48") (pinfunction "PB9_48") (pintype "passive"))
    )
    (net (code "144") (name "unconnected-(U2-PB10-Pad22)") (class "Default")
      (node (ref "U2") (pin "22") (pinfunction "PB10_22") (pintype "passive"))
    )
    (net (code "145") (name "unconnected-(U2-PB11-Pad23)") (class "Default")
      (node (ref "U2") (pin "23") (pinfunction "PB11_23") (pintype "passive"))
    )
    (net (code "146") (name "unconnected-(U2-PB12-Pad24)") (class "Default")
      (node (ref "U2") (pin "24") (pinfunction "PB12_24") (pintype "passive"))
    )
    (net (code "147") (name "unconnected-(U2-PB13-Pad25)") (class "Default")
      (node (ref "U2") (pin "25") (pinfunction "PB13_25") (pintype "passive"))
    )
    (net (code "148") (name "unconnected-(U2-PB14-Pad26)") (class "Default")
      (node (ref "U2") (pin "26") (pinfunction "PB14_26") (pintype "passive"))
    )
    (net (code "149") (name "unconnected-(U2-PB15-Pad27)") (class "Default")
      (node (ref "U2") (pin "27") (pinfunction "PB15_27") (pintype "passive"))
    )
    (net (code "150") (name "unconnected-(U2-PC6-Pad30)") (class "Default")
      (node (ref "U2") (pin "30") (pinfunction "PC6_30") (pintype "passive"))
    )
    (net (code "151") (name "unconnected-(U2-PC7-Pad31)") (class "Default")
      (node (ref "U2") (pin "31") (pinfunction "PC7_31") (pintype "passive"))
    )
    (net (code "152") (name "unconnected-(U2-PC13-Pad1)") (class "Default")
      (node (ref "U2") (pin "1") (pinfunction "PC13_1") (pintype "passive"))
    )
    (net (code "153") (name "unconnected-(U2-PC14-OSC32_IN-Pad2)") (class "Default")
      (node (ref "U2") (pin "2") (pinfunction "PC14-OSC32_IN_2") (pintype "passive"))
    )
    (net (code "154") (name "unconnected-(U2-PC15-OSC32_OUT-Pad3)") (class "Default")
      (node (ref "U2") (pin "3") (pinfunction "PC15-OSC32_OUT_3") (pintype "passive"))
    )
    (net (code "155") (name "unconnected-(U2-PD0-Pad38)") (class "Default")
      (node (ref "U2") (pin "38") (pinfunction "PD0_38") (pintype "passive"))
    )
    (net (code "156") (name "unconnected-(U2-PD1-Pad39)") (class "Default")
      (node (ref "U2") (pin "39") (pinfunction "PD1_39") (pintype "passive"))
    )
    (net (code "157") (name "unconnected-(U2-PD2-Pad40)") (class "Default")
      (node (ref "U2") (pin "40") (pinfunction "PD2_40") (pintype "passive"))
    )
    (net (code "158") (name "unconnected-(U2-PD3-Pad41)") (class "Default")
      (node (ref "U2") (pin "41") (pinfunction "PD3_41") (pintype "passive"))
    )
    (net (code "159") (name "unconnected-(U2-PF0-OSC_IN-Pad8)") (class "Default")
      (node (ref "U2") (pin "8") (pinfunction "PF0-OSC_IN_8") (pintype "passive"))
    )
    (net (code "160") (name "unconnected-(U2-PF1-OSC_OUT-Pad9)") (class "Default")
      (node (ref "U2") (pin "9") (pinfunction "PF1-OSC_OUT_9") (pintype "passive"))
    )
    (net (code "161") (name "unconnected-(U2-PF2-NRST-Pad10)") (class "Default")
      (node (ref "U2") (pin "10") (pinfunction "PF2-NRST_10") (pintype "passive"))
    )
    (net (code "162") (name "unconnected-(U2-VBAT-Pad4)") (class "Default")
      (node (ref "U2") (pin "4") (pinfunction "VBAT_4") (pintype "passive"))
    )
    (net (code "163") (name "unconnected-(U2-VDD{slash}VDDA-Pad6)") (class "Default")
      (node (ref "U2") (pin "6") (pinfunction "VDD/VDDA_6") (pintype "passive"))
    )
    (net (code "164") (name "unconnected-(U2-VREF+-Pad5)") (class "Default")
      (node (ref "U2") (pin "5") (pinfunction "VREF+_5") (pintype "passive"))
    )
    (net (code "165") (name "unconnected-(U2-VSS{slash}VSSA-Pad7)") (class "Default")
      (node (ref "U2") (pin "7") (pinfunction "VSS/VSSA_7") (pintype "passive"))
    )
    (net (code "166") (name "unconnected-(U3-ACN-Pad2)") (class "Default")
      (node (ref "U3") (pin "2") (pinfunction "ACN_2") (pintype "passive"))
    )
    (net (code "167") (name "unconnected-(U3-ACP-Pad3)") (class "Default")
      (node (ref "U3") (pin "3") (pinfunction "ACP_3") (pintype "passive"))
    )
    (net (code "168") (name "unconnected-(U3-BATDRV-Pad21)") (class "Default")
      (node (ref "U3") (pin "21") (pinfunction "BATDRV_21") (pintype "passive"))
    )
    (net (code "169") (name "unconnected-(U3-BTST1-Pad30)") (class "Default")
      (node (ref "U3") (pin "30") (pinfunction "BTST1_30") (pintype "passive"))
    )
    (net (code "170") (name "unconnected-(U3-BTST2-Pad25)") (class "Default")
      (node (ref "U3") (pin "25") (pinfunction "BTST2_25") (pintype "passive"))
    )
    (net (code "171") (name "unconnected-(U3-CELL_BATPRESZ-Pad18)") (class "Default")
      (node (ref "U3") (pin "18") (pinfunction "CELL_BATPRESZ_18") (pintype "passive"))
    )
    (net (code "172") (name "unconnected-(U3-CHRG_OK-Pad4)") (class "Default")
      (node (ref "U3") (pin "4") (pinfunction "CHRG_OK_4") (pintype "passive"))
    )
    (net (code "173") (name "unconnected-(U3-CMPIN-Pad14)") (class "Default")
      (node (ref "U3") (pin "14") (pinfunction "CMPIN_14") (pintype "passive"))
    )
    (net (code "174") (name "unconnected-(U3-CMPOUT-Pad15)") (class "Default")
      (node (ref "U3") (pin "15") (pinfunction "CMPOUT_15") (pintype "passive"))
    )
    (net (code "175") (name "unconnected-(U3-COMP1-Pad16)") (class "Default")
      (node (ref "U3") (pin "16") (pinfunction "COMP1_16") (pintype "passive"))
    )
    (net (code "176") (name "unconnected-(U3-COMP2-Pad17)") (class "Default")
      (node (ref "U3") (pin "17") (pinfunction "COMP2_17") (pintype "passive"))
    )
    (net (code "177") (name "unconnected-(U3-EN_OTG-Pad5)") (class "Default")
      (node (ref "U3") (pin "5") (pinfunction "EN_OTG_5") (pintype "passive"))
    )
    (net (code "178") (name "unconnected-(U3-EPAD-Pad33)") (class "Default")
      (node (ref "U3") (pin "33") (pinfunction "EPAD_33") (pintype "passive"))
    )
    (net (code "179") (name "unconnected-(U3-HIDRV1-Pad31)") (class "Default")
      (node (ref "U3") (pin "31") (pinfunction "HIDRV1_31") (pintype "passive"))
    )
    (net (code "180") (name "unconnected-(U3-HIDRV2-Pad24)") (class "Default")
      (node (ref "U3") (pin "24") (pinfunction "HIDRV2_24") (pintype "passive"))
    )
    (net (code "181") (name "unconnected-(U3-IADPT-Pad8)") (class "Default")
      (node (ref "U3") (pin "8") (pinfunction "IADPT_8") (pintype "passive"))
    )
    (net (code "182") (name "unconnected-(U3-IBAT-Pad9)") (class "Default")
      (node (ref "U3") (pin "9") (pinfunction "IBAT_9") (pintype "passive"))
    )
    (net (code "183") (name "unconnected-(U3-ILIM_HIZ-Pad6)") (class "Default")
      (node (ref "U3") (pin "6") (pinfunction "ILIM_HIZ_6") (pintype "passive"))
    )
    (net (code "184") (name "unconnected-(U3-LODRV1-Pad29)") (class "Default")
      (node (ref "U3") (pin "29") (pinfunction "LODRV1_29") (pintype "passive"))
    )
    (net (code "185") (name "unconnected-(U3-LODRV2-Pad26)") (class "Default")
      (node (ref "U3") (pin "26") (pinfunction "LODRV2_26") (pintype "passive"))
    )
    (net (code "186") (name "unconnected-(U3-PGND-Pad27)") (class "Default")
      (node (ref "U3") (pin "27") (pinfunction "PGND_27") (pintype "passive"))
    )
    (net (code "187") (name "unconnected-(U3-PROCHOT-Pad11)") (class "Default")
      (node (ref "U3") (pin "11") (pinfunction "PROCHOT_11") (pintype "passive"))
    )
    (net (code "188") (name "unconnected-(U3-PSYS-Pad10)") (class "Default")
      (node (ref "U3") (pin "10") (pinfunction "PSYS_10") (pintype "passive"))
    )
    (net (code "189") (name "unconnected-(U3-REGN-Pad28)") (class "Default")
      (node (ref "U3") (pin "28") (pinfunction "REGN_28") (pintype "passive"))
    )
    (net (code "190") (name "unconnected-(U3-SCL-Pad13)") (class "Default")
      (node (ref "U3") (pin "13") (pinfunction "SCL_13") (pintype "passive"))
    )
    (net (code "191") (name "unconnected-(U3-SDA-Pad12)") (class "Default")
      (node (ref "U3") (pin "12") (pinfunction "SDA_12") (pintype "passive"))
    )
    (net (code "192") (name "unconnected-(U3-SRN-Pad19)") (class "Default")
      (node (ref "U3") (pin "19") (pinfunction "SRN_19") (pintype "passive"))
    )
    (net (code "193") (name "unconnected-(U3-SRP-Pad20)") (class "Default")
      (node (ref "U3") (pin "20") (pinfunction "SRP_20") (pintype "passive"))
    )
    (net (code "194") (name "unconnected-(U3-SW1-Pad32)") (class "Default")
      (node (ref "U3") (pin "32") (pinfunction "SW1_32") (pintype "passive"))
    )
    (net (code "195") (name "unconnected-(U3-SW2-Pad23)") (class "Default")
      (node (ref "U3") (pin "23") (pinfunction "SW2_23") (pintype "passive"))
    )
    (net (code "196") (name "unconnected-(U3-VBUS-Pad1)") (class "Default")
      (node (ref "U3") (pin "1") (pinfunction "VBUS_1") (pintype "passive"))
    )
    (net (code "197") (name "unconnected-(U3-VDDA-Pad7)") (class "Default")
      (node (ref "U3") (pin "7") (pinfunction "VDDA_7") (pintype "passive"))
    )
    (net (code "198") (name "unconnected-(U3-VSYS-Pad22)") (class "Default")
      (node (ref "U3") (pin "22") (pinfunction "VSYS_22") (pintype "passive"))
    )
    (net (code "199") (name "unconnected-(U4-GND-Pad1)") (class "Default")
      (node (ref "U4") (pin "1") (pinfunction "GND_1") (pintype "passive"))
    )
    (net (code "200") (name "unconnected-(U4-VIN-Pad3)") (class "Default")
      (node (ref "U4") (pin "3") (pinfunction "VIN_3") (pintype "passive"))
    )
    (net (code "201") (name "unconnected-(U4-VOUT-Pad2)") (class "Default")
      (node (ref "U4") (pin "2") (pinfunction "VOUT_2") (pintype "passive"))
    )
  )
)
